# PX4FMUv1_7_1.net
KiCad netlist of a schematic drawn in EAGLE
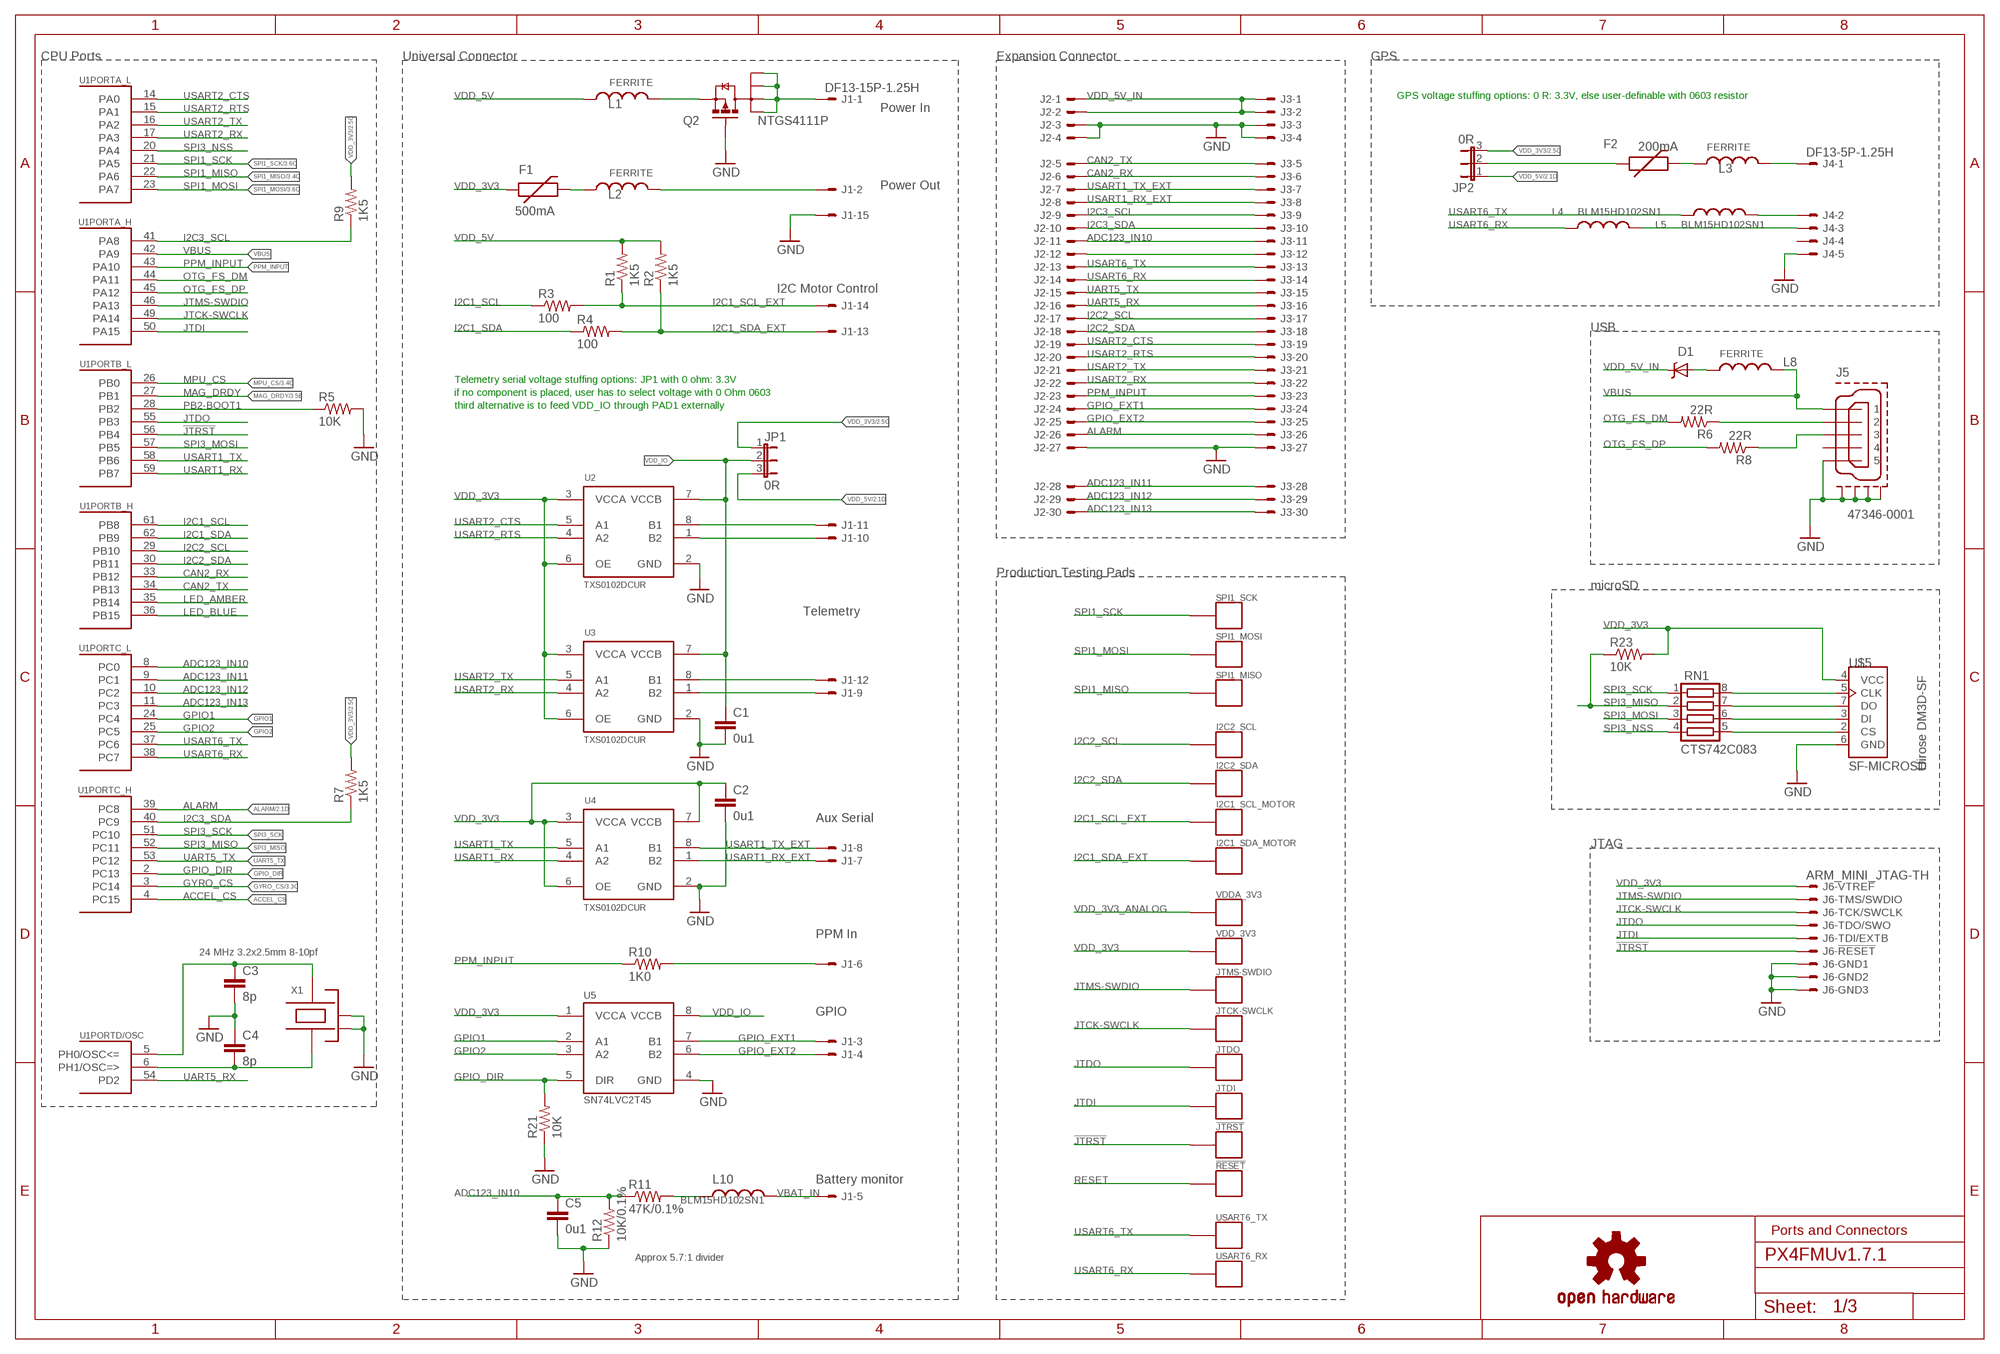
[diagram p0: schematic, sheet 1]
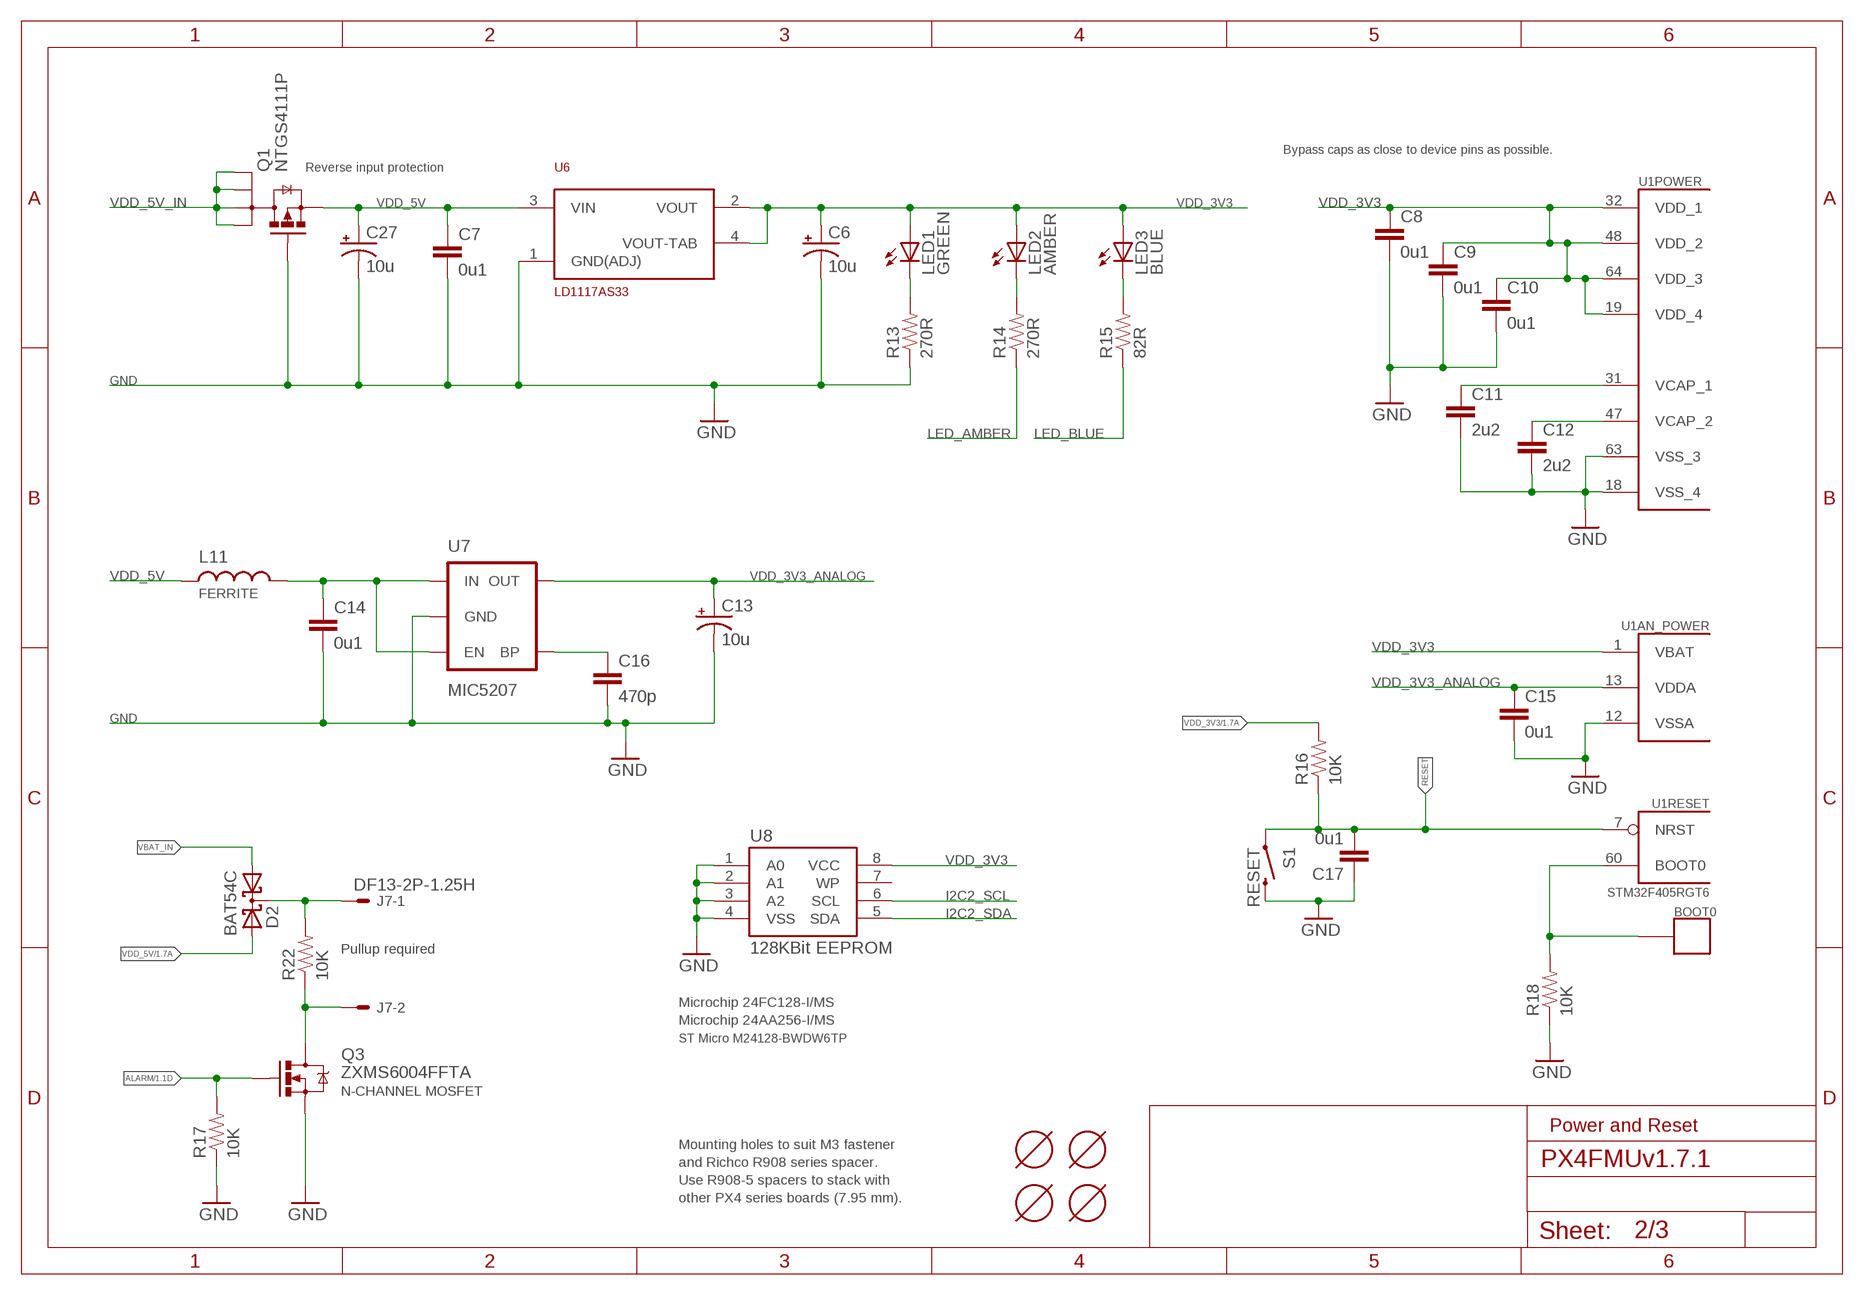
[diagram p1: schematic, sheet 2]
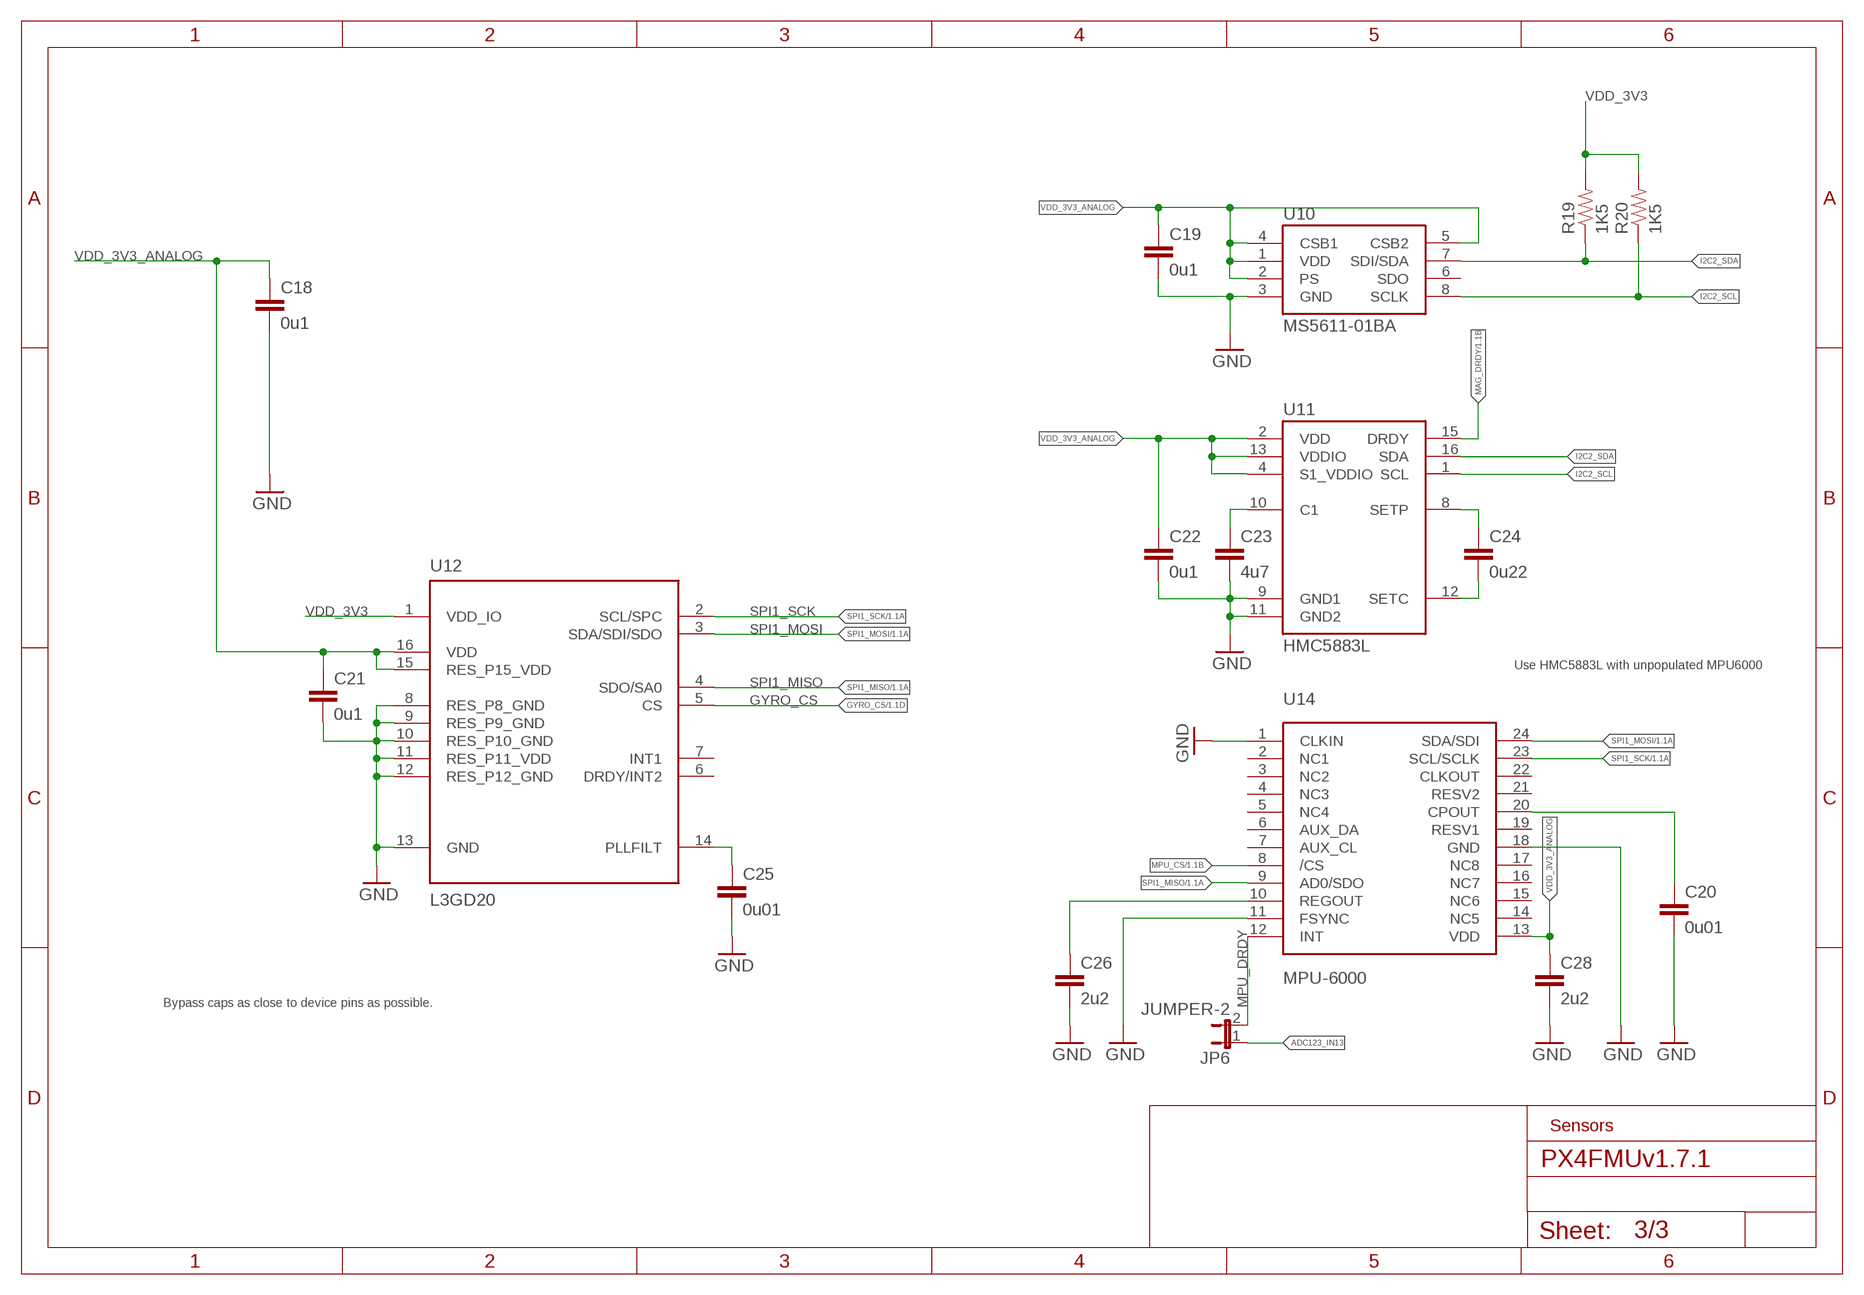
[diagram p2: schematic, sheet 3]

(export (version "E")
  (design (tool "Eeschema 10.0.6"))
  (components
    (comp (ref "C18")
      (value "0u1")
      (footprint "eagle-import:0402-CAP")
      (fields (field (name "PARTNO") "CC0402ZRY5V7BB104"))
      (libsource (lib "eagle-import") (part "CAP0402-CAP"))
    )
    (comp (ref "C19")
      (value "0u1")
      (footprint "eagle-import:0402-CAP")
      (fields (field (name "PARTNO") "CC0402ZRY5V7BB104"))
      (libsource (lib "eagle-import") (part "CAP0402-CAP"))
    )
    (comp (ref "C20")
      (value "0u01")
      (footprint "eagle-import:0402-CAP")
      (fields (field (name "PARTNO") "CC0402KRX7R7BB103"))
      (libsource (lib "eagle-import") (part "CAP0402-CAP"))
    )
    (comp (ref "C21")
      (value "0u1")
      (footprint "eagle-import:0402-CAP")
      (fields (field (name "PARTNO") "CC0402ZRY5V7BB104"))
      (libsource (lib "eagle-import") (part "CAP0402-CAP"))
    )
    (comp (ref "C22")
      (value "0u1")
      (footprint "eagle-import:0402-CAP")
      (fields (field (name "PARTNO") "CC0402ZRY5V7BB104"))
      (libsource (lib "eagle-import") (part "CAP0402-CAP"))
    )
    (comp (ref "C23")
      (value "4u7")
      (footprint "eagle-import:0402-CAP")
      (fields (field (name "PARTNO") "C1608Y5V0J475Z"))
      (libsource (lib "eagle-import") (part "CAP0402-CAP"))
    )
    (comp (ref "C24")
      (value "0u22")
      (footprint "eagle-import:0402-CAP")
      (fields (field (name "PARTNO") "C1005Y5V1C224Z"))
      (libsource (lib "eagle-import") (part "CAP0402-CAP"))
    )
    (comp (ref "C25")
      (value "0u01")
      (footprint "eagle-import:0402-CAP")
      (fields (field (name "PARTNO") "CC0402KRX7R7BB103"))
      (libsource (lib "eagle-import") (part "CAP0402-CAP"))
    )
    (comp (ref "C26")
      (value "2u2")
      (footprint "eagle-import:0402-CAP")
      (fields (field (name "PARTNO") "C1608Y5V1C225Z"))
      (libsource (lib "eagle-import") (part "CAP0402-CAP"))
    )
    (comp (ref "C28")
      (value "2u2")
      (footprint "eagle-import:0402-CAP")
      (fields (field (name "PARTNO") "C1608Y5V1C225Z"))
      (libsource (lib "eagle-import") (part "CAP0402-CAP"))
    )
    (comp (ref "JP6")
      (value "JUMPER-2")
      (footprint "eagle-import:SJ_2")
      (libsource (lib "eagle-import") (part "JUMPER-2"))
    )
    (comp (ref "R19")
      (value "1K5")
      (footprint "eagle-import:0402-RES")
      (fields (field (name "PARTNO") "RMCF0402JT1K50"))
      (libsource (lib "eagle-import") (part "RESISTOR0402-RES"))
    )
    (comp (ref "R20")
      (value "1K5")
      (footprint "eagle-import:0402-RES")
      (fields (field (name "PARTNO") "RMCF0402JT1K50"))
      (libsource (lib "eagle-import") (part "RESISTOR0402-RES"))
    )
    (comp (ref "U10")
      (value "MS5611-01BA")
      (footprint "eagle-import:MS5611-01BA")
      (libsource (lib "eagle-import") (part "MS5611-01BA"))
    )
    (comp (ref "U11")
      (value "HMC5883L")
      (footprint "eagle-import:HMC5883L-MAN")
      (libsource (lib "eagle-import") (part "HMC5883L"))
    )
    (comp (ref "U12")
      (value "L3GD20")
      (footprint "eagle-import:L3G4200DH-MAN")
      (libsource (lib "eagle-import") (part "L3G4200DH-LL"))
    )
    (comp (ref "U14")
      (value "MPU-6000")
      (footprint "eagle-import:QFN-24")
      (libsource (lib "eagle-import") (part "MPU-6000"))
    )
    (comp (ref "BOOT0")
      (value "PAD.04")
      (footprint "eagle-import:PAD.04X.04")
      (libsource (lib "eagle-import") (part "PAD.04"))
    )
    (comp (ref "C6")
      (value "10u")
      (footprint "eagle-import:EIA3216")
      (fields (field (name "PARTNO") "F931A106MAA"))
      (libsource (lib "eagle-import") (part "CAP_POL1206"))
    )
    (comp (ref "C7")
      (value "0u1")
      (footprint "eagle-import:0402-CAP")
      (fields (field (name "PARTNO") "CC0402ZRY5V7BB104"))
      (libsource (lib "eagle-import") (part "CAP0402-CAP"))
    )
    (comp (ref "C8")
      (value "0u1")
      (footprint "eagle-import:0402-CAP")
      (fields (field (name "PARTNO") "CC0402ZRY5V7BB104"))
      (libsource (lib "eagle-import") (part "CAP0402-CAP"))
    )
    (comp (ref "C9")
      (value "0u1")
      (footprint "eagle-import:0402-CAP")
      (fields (field (name "PARTNO") "CC0402ZRY5V7BB104"))
      (libsource (lib "eagle-import") (part "CAP0402-CAP"))
    )
    (comp (ref "C10")
      (value "0u1")
      (footprint "eagle-import:0402-CAP")
      (fields (field (name "PARTNO") "CC0402ZRY5V7BB104"))
      (libsource (lib "eagle-import") (part "CAP0402-CAP"))
    )
    (comp (ref "C11")
      (value "2u2")
      (footprint "eagle-import:0402-CAP")
      (fields (field (name "PARTNO") "C1608Y5V1C225Z"))
      (libsource (lib "eagle-import") (part "CAP0402-CAP"))
    )
    (comp (ref "C12")
      (value "2u2")
      (footprint "eagle-import:0402-CAP")
      (fields (field (name "PARTNO") "C1608Y5V1C225Z"))
      (libsource (lib "eagle-import") (part "CAP0402-CAP"))
    )
    (comp (ref "C13")
      (value "10u")
      (footprint "eagle-import:EIA3216")
      (fields (field (name "PARTNO") "F931A106MAA"))
      (libsource (lib "eagle-import") (part "CAP_POL1206"))
    )
    (comp (ref "C14")
      (value "0u1")
      (footprint "eagle-import:0402-CAP")
      (fields (field (name "PARTNO") "CC0402ZRY5V7BB104"))
      (libsource (lib "eagle-import") (part "CAP0402-CAP"))
    )
    (comp (ref "C15")
      (value "0u1")
      (footprint "eagle-import:0402-CAP")
      (fields (field (name "PARTNO") "CC0402ZRY5V7BB104"))
      (libsource (lib "eagle-import") (part "CAP0402-CAP"))
    )
    (comp (ref "C16")
      (value "470p")
      (footprint "eagle-import:0402-CAP")
      (fields (field (name "PARTNO") "CC0402KRX7R9BB471"))
      (libsource (lib "eagle-import") (part "CAP0402-CAP"))
    )
    (comp (ref "C17")
      (value "0u1")
      (footprint "eagle-import:0402-CAP")
      (fields (field (name "PARTNO") "CC0402ZRY5V7BB104"))
      (libsource (lib "eagle-import") (part "CAP0402-CAP"))
    )
    (comp (ref "C27")
      (value "10u")
      (footprint "eagle-import:EIA3216")
      (fields (field (name "PARTNO") "F931A106MAA"))
      (libsource (lib "eagle-import") (part "CAP_POL1206"))
    )
    (comp (ref "D2")
      (value "BAT54C")
      (footprint "eagle-import:SOT23-3")
      (fields (field (name "PARTNO") "BAT54C-7-F"))
      (libsource (lib "eagle-import") (part "BAT54C"))
    )
    (comp (ref "J7")
      (value "DF13-2P-1.25H")
      (footprint "eagle-import:DF13A-2P-1.25H")
      (fields (field (name "PARTNO") "DF13-2P-1.25H(20)"))
      (libsource (lib "eagle-import") (part "DF13-2P-1.25?H"))
    )
    (comp (ref "L11")
      (value "FERRITE")
      (footprint "eagle-import:0402-IND")
      (fields (field (name "PARTNO") "BKP1005HS121-T"))
      (libsource (lib "eagle-import") (part "INDUCTOR0402"))
    )
    (comp (ref "LED1")
      (value "GREEN")
      (footprint "eagle-import:LED-0603")
      (fields (field (name "PARTNO") "LNJ337W83RA"))
      (libsource (lib "eagle-import") (part "LED0603"))
    )
    (comp (ref "LED2")
      (value "AMBER")
      (footprint "eagle-import:LED-0603")
      (fields (field (name "PARTNO") "LNJ437W84RA"))
      (libsource (lib "eagle-import") (part "LED0603"))
    )
    (comp (ref "LED3")
      (value "BLUE")
      (footprint "eagle-import:LED-0603")
      (fields (field (name "PARTNO") "LNJ937W8CRA"))
      (libsource (lib "eagle-import") (part "LED0603"))
    )
    (comp (ref "Q1")
      (value "NTGS4111P")
      (footprint "eagle-import:TSOP-6")
      (libsource (lib "eagle-import") (part "NTGS4111P"))
    )
    (comp (ref "Q3")
      (value "ZXMS6004FFTA")
      (footprint "eagle-import:SOT23-3")
      (libsource (lib "eagle-import") (part "MOSFET-NCHANNELSMD"))
    )
    (comp (ref "R13")
      (value "270R")
      (footprint "eagle-import:0402-RES")
      (fields (field (name "PARTNO") "RC0402JR-07270RL"))
      (libsource (lib "eagle-import") (part "RESISTOR0402-RES"))
    )
    (comp (ref "R14")
      (value "270R")
      (footprint "eagle-import:0402-RES")
      (fields (field (name "PARTNO") "RC0402JR-07270RL"))
      (libsource (lib "eagle-import") (part "RESISTOR0402-RES"))
    )
    (comp (ref "R15")
      (value "82R")
      (footprint "eagle-import:0402-RES")
      (fields (field (name "PARTNO") "RC0402JR-0782RL"))
      (libsource (lib "eagle-import") (part "RESISTOR0402-RES"))
    )
    (comp (ref "R16")
      (value "10K")
      (footprint "eagle-import:0402-RES")
      (fields (field (name "PARTNO") "RMCF0402FT10K0"))
      (libsource (lib "eagle-import") (part "RESISTOR0402-RES"))
    )
    (comp (ref "R17")
      (value "10K")
      (footprint "eagle-import:0402-RES")
      (fields (field (name "PARTNO") "RMCF0402FT10K0"))
      (libsource (lib "eagle-import") (part "RESISTOR0402-RES"))
    )
    (comp (ref "R18")
      (value "10K")
      (footprint "eagle-import:0402-RES")
      (fields (field (name "PARTNO") "RMCF0402FT10K0"))
      (libsource (lib "eagle-import") (part "RESISTOR0402-RES"))
    )
    (comp (ref "R22")
      (value "10K")
      (footprint "eagle-import:0402-RES")
      (fields (field (name "PARTNO") "RMCF0402FT10K0"))
      (libsource (lib "eagle-import") (part "RESISTOR0402-RES"))
    )
    (comp (ref "S1")
      (value "RESET")
      (footprint "eagle-import:EVQP7J01K")
      (fields (field (name "PARTNO") "EVQP7J01K"))
      (libsource (lib "eagle-import") (part "SWITCH-MOMENTARY-2"))
    )
    (comp (ref "U$1")
      (value "MOUNT-HOLE3.1MM")
      (footprint "eagle-import:MOUNT-HOLE3.1")
      (libsource (lib "eagle-import") (part "MOUNT-HOLE3.1MM"))
    )
    (comp (ref "U$2")
      (value "MOUNT-HOLE3.1MM")
      (footprint "eagle-import:MOUNT-HOLE3.1")
      (libsource (lib "eagle-import") (part "MOUNT-HOLE3.1MM"))
    )
    (comp (ref "U$3")
      (value "MOUNT-HOLE3.1MM")
      (footprint "eagle-import:MOUNT-HOLE3.1")
      (libsource (lib "eagle-import") (part "MOUNT-HOLE3.1MM"))
    )
    (comp (ref "U$4")
      (value "MOUNT-HOLE3.1MM")
      (footprint "eagle-import:MOUNT-HOLE3.1")
      (libsource (lib "eagle-import") (part "MOUNT-HOLE3.1MM"))
    )
    (comp (ref "U1")
      (value "STM32F405RGT6")
      (footprint "eagle-import:TQFP64")
      (fields (field (name "PARTNO") "STM32F405RGT6"))
      (libsource (lib "eagle-import") (part "STM32F20X_TQFP64"))
    )
    (comp (ref "U6")
      (value "LD1117AS33")
      (footprint "eagle-import:SOT-223")
      (libsource (lib "eagle-import") (part "LD1117AS33"))
    )
    (comp (ref "U7")
      (value "MIC5207")
      (footprint "eagle-import:SOT23-5")
      (fields (field (name "PARTNO") "MIC5207-3.3YM5"))
      (libsource (lib "eagle-import") (part "V_REG_LDOSMD"))
    )
    (comp (ref "U8")
      (value "128KBit EEPROM")
      (footprint "eagle-import:MSOP-8")
      (fields (field (name "PARTNO") "24FC128-I/MS"))
      (libsource (lib "eagle-import") (part "EEPROM-I2CMSOP"))
    )
    (comp (ref "!JTRST")
      (value "PAD.04")
      (footprint "eagle-import:PAD.04X.04")
      (libsource (lib "eagle-import") (part "PAD.04"))
    )
    (comp (ref "!RESET")
      (value "PAD.04")
      (footprint "eagle-import:PAD.04X.04")
      (libsource (lib "eagle-import") (part "PAD.04"))
    )
    (comp (ref "C1")
      (value "0u1")
      (footprint "eagle-import:0402-CAP")
      (fields (field (name "PARTNO") "CC0402ZRY5V7BB104"))
      (libsource (lib "eagle-import") (part "CAP0402-CAP"))
    )
    (comp (ref "C2")
      (value "0u1")
      (footprint "eagle-import:0402-CAP")
      (fields (field (name "PARTNO") "CC0402ZRY5V7BB104"))
      (libsource (lib "eagle-import") (part "CAP0402-CAP"))
    )
    (comp (ref "C3")
      (value "8p")
      (footprint "eagle-import:0402-CAP")
      (fields (field (name "PARTNO") "C1005C0G1H080C"))
      (libsource (lib "eagle-import") (part "CAP0402-CAP"))
    )
    (comp (ref "C4")
      (value "8p")
      (footprint "eagle-import:0402-CAP")
      (fields (field (name "PARTNO") "C1005C0G1H080C"))
      (libsource (lib "eagle-import") (part "CAP0402-CAP"))
    )
    (comp (ref "C5")
      (value "0u1")
      (footprint "eagle-import:0402-CAP")
      (fields (field (name "PARTNO") "CC0402ZRY5V7BB104"))
      (libsource (lib "eagle-import") (part "CAP0402-CAP"))
    )
    (comp (ref "D1")
      (value "MSS1P4-M3")
      (footprint "eagle-import:MICROSMP")
      (fields (field (name "PARTNO") "MSS1P4-M3/89A"))
      (libsource (lib "eagle-import") (part "DIODE-SCHOTTKY_MSMP"))
    )
    (comp (ref "F1")
      (value "500mA")
      (footprint "eagle-import:0402-PTC")
      (fields (field (name "PARTNO") "MF-FSMF050X-2"))
      (libsource (lib "eagle-import") (part "PTC0402"))
    )
    (comp (ref "F2")
      (value "200mA")
      (footprint "eagle-import:0402-PTC")
      (fields (field (name "PARTNO") "MF-FSMF020X-2"))
      (libsource (lib "eagle-import") (part "PTC0402"))
    )
    (comp (ref "I2C1_SCL_MOTOR")
      (value "PAD.03")
      (footprint "eagle-import:PAD.03X.03")
      (libsource (lib "eagle-import") (part "PAD.03"))
    )
    (comp (ref "I2C1_SDA_MOTOR")
      (value "PAD.03")
      (footprint "eagle-import:PAD.03X.03")
      (libsource (lib "eagle-import") (part "PAD.03"))
    )
    (comp (ref "I2C2_SCL")
      (value "PAD.03")
      (footprint "eagle-import:PAD.03X.03")
      (libsource (lib "eagle-import") (part "PAD.03"))
    )
    (comp (ref "I2C2_SDA")
      (value "PAD.04")
      (footprint "eagle-import:PAD.04X.04")
      (libsource (lib "eagle-import") (part "PAD.04"))
    )
    (comp (ref "J1")
      (value "DF13-15P-1.25H")
      (footprint "eagle-import:DF13A-15P-1.25H")
      (fields (field (name "PARTNO") "DF13A-15P-1.25H(20)"))
      (libsource (lib "eagle-import") (part "DF13-15P-1.25?H"))
    )
    (comp (ref "J2")
      (value "HEADER_2X15-REV")
      (footprint "eagle-import:HEADER_2MM_2X15_REVERSE")
      (fields (field (name "BOM") "EXCLUDE") (field (name "PARTNO") "953230-2000-AR-PR"))
      (libsource (lib "eagle-import") (part "HEADER_2X15-REV"))
    )
    (comp (ref "J3")
      (value "HEADER_2X15")
      (footprint "eagle-import:HEADER_2MM_2X15")
      (fields (field (name "PARTNO") "953230-2000-AR-PR"))
      (libsource (lib "eagle-import") (part "HEADER_2X15-SMD"))
    )
    (comp (ref "J4")
      (value "DF13-5P-1.25H")
      (footprint "eagle-import:DF13A-5P-1.25H")
      (fields (field (name "PARTNO") "DF13A-5P-1.25H(20)"))
      (libsource (lib "eagle-import") (part "DF13-5P-1.25?H"))
    )
    (comp (ref "J5")
      (value "47346-0001")
      (footprint "eagle-import:MOLEX-47346-0001")
      (libsource (lib "eagle-import") (part "MOLEX-47346-0001"))
    )
    (comp (ref "J6")
      (value "ARM_MINI_JTAG-TH")
      (footprint "eagle-import:FTSH-105-01-XXX-DV")
      (fields (field (name "PARTNO") "M50-3900542"))
      (libsource (lib "eagle-import") (part "ARM_MINI_JTAG-TH"))
    )
    (comp (ref "JP1")
      (value "0R")
      (footprint "eagle-import:SJ_3_0603_PASTE1&2")
      (fields (field (name "PARTNO") "RMCF0402ZT0R00"))
      (libsource (lib "eagle-import") (part "JUMPER-30603"))
    )
    (comp (ref "JP2")
      (value "0R")
      (footprint "eagle-import:SJ_3_0603_PASTE1&2")
      (fields (field (name "PARTNO") "RMCF0402ZT0R00"))
      (libsource (lib "eagle-import") (part "JUMPER-30603"))
    )
    (comp (ref "JTCK-SWCLK")
      (value "PAD.04")
      (footprint "eagle-import:PAD.04X.04")
      (libsource (lib "eagle-import") (part "PAD.04"))
    )
    (comp (ref "JTDI")
      (value "PAD.04")
      (footprint "eagle-import:PAD.04X.04")
      (libsource (lib "eagle-import") (part "PAD.04"))
    )
    (comp (ref "JTDO")
      (value "PAD.04")
      (footprint "eagle-import:PAD.04X.04")
      (libsource (lib "eagle-import") (part "PAD.04"))
    )
    (comp (ref "JTMS-SWDIO")
      (value "PAD.04")
      (footprint "eagle-import:PAD.04X.04")
      (libsource (lib "eagle-import") (part "PAD.04"))
    )
    (comp (ref "L1")
      (value "FERRITE")
      (footprint "eagle-import:0402-IND")
      (fields (field (name "PARTNO") "BKP1005HS121-T"))
      (libsource (lib "eagle-import") (part "INDUCTOR0402"))
    )
    (comp (ref "L2")
      (value "FERRITE")
      (footprint "eagle-import:0402-IND")
      (fields (field (name "PARTNO") "BKP1005HS121-T"))
      (libsource (lib "eagle-import") (part "INDUCTOR0402"))
    )
    (comp (ref "L3")
      (value "FERRITE")
      (footprint "eagle-import:0402-IND")
      (fields (field (name "PARTNO") "BKP1005HS121-T"))
      (libsource (lib "eagle-import") (part "INDUCTOR0402"))
    )
    (comp (ref "L4")
      (value "BLM15HD102SN1")
      (footprint "eagle-import:0402-IND")
      (libsource (lib "eagle-import") (part "INDUCTOR0402"))
    )
    (comp (ref "L5")
      (value "BLM15HD102SN1")
      (footprint "eagle-import:0402-IND")
      (libsource (lib "eagle-import") (part "INDUCTOR0402"))
    )
    (comp (ref "L8")
      (value "FERRITE")
      (footprint "eagle-import:0402-IND")
      (fields (field (name "PARTNO") "BKP1005HS121-T"))
      (libsource (lib "eagle-import") (part "INDUCTOR0402"))
    )
    (comp (ref "L10")
      (value "BLM15HD102SN1")
      (footprint "eagle-import:0402-IND")
      (libsource (lib "eagle-import") (part "INDUCTOR0402"))
    )
    (comp (ref "Q2")
      (value "NTGS4111P")
      (footprint "eagle-import:TSOP-6")
      (libsource (lib "eagle-import") (part "NTGS4111P"))
    )
    (comp (ref "R1")
      (value "1K5")
      (footprint "eagle-import:0402-RES")
      (fields (field (name "PARTNO") "RMCF0402JT1K50"))
      (libsource (lib "eagle-import") (part "RESISTOR0402-RES"))
    )
    (comp (ref "R2")
      (value "1K5")
      (footprint "eagle-import:0402-RES")
      (fields (field (name "PARTNO") "RMCF0402JT1K50"))
      (libsource (lib "eagle-import") (part "RESISTOR0402-RES"))
    )
    (comp (ref "R3")
      (value "100")
      (footprint "eagle-import:0402-RES")
      (fields (field (name "PARTNO") "RMCF0402JT100R"))
      (libsource (lib "eagle-import") (part "RESISTOR0402-RES"))
    )
    (comp (ref "R4")
      (value "100")
      (footprint "eagle-import:0402-RES")
      (fields (field (name "PARTNO") "RMCF0402JT100R"))
      (libsource (lib "eagle-import") (part "RESISTOR0402-RES"))
    )
    (comp (ref "R5")
      (value "10K")
      (footprint "eagle-import:0402-RES")
      (fields (field (name "PARTNO") "RMCF0402FT10K0"))
      (libsource (lib "eagle-import") (part "RESISTOR0402-RES"))
    )
    (comp (ref "R6")
      (value "22R")
      (footprint "eagle-import:0402-RES")
      (fields (field (name "PARTNO") "RMCF0402JT22R0"))
      (libsource (lib "eagle-import") (part "RESISTOR0402-RES"))
    )
    (comp (ref "R7")
      (value "1K5")
      (footprint "eagle-import:0402-RES")
      (fields (field (name "PARTNO") "RMCF0402JT1K50"))
      (libsource (lib "eagle-import") (part "RESISTOR0402-RES"))
    )
    (comp (ref "R8")
      (value "22R")
      (footprint "eagle-import:0402-RES")
      (fields (field (name "PARTNO") "RMCF0402JT22R0"))
      (libsource (lib "eagle-import") (part "RESISTOR0402-RES"))
    )
    (comp (ref "R9")
      (value "1K5")
      (footprint "eagle-import:0402-RES")
      (fields (field (name "PARTNO") "RMCF0402JT1K50"))
      (libsource (lib "eagle-import") (part "RESISTOR0402-RES"))
    )
    (comp (ref "R10")
      (value "1K0")
      (footprint "eagle-import:0402-RES")
      (fields (field (name "PARTNO") "RMCF0402JT1K00"))
      (libsource (lib "eagle-import") (part "RESISTOR0402-RES"))
    )
    (comp (ref "R11")
      (value "47K/0.1%")
      (footprint "eagle-import:0402-RES")
      (fields (field (name "PARTNO") "ERA-2AEB473X"))
      (libsource (lib "eagle-import") (part "RESISTOR0402-RES"))
    )
    (comp (ref "R12")
      (value "10K/0.1%")
      (footprint "eagle-import:0402-RES")
      (fields (field (name "PARTNO") "ERA-2AEB103X"))
      (libsource (lib "eagle-import") (part "RESISTOR0402-RES"))
    )
    (comp (ref "R21")
      (value "10K")
      (footprint "eagle-import:0402-RES")
      (fields (field (name "PARTNO") "RMCF0402FT10K0"))
      (libsource (lib "eagle-import") (part "RESISTOR0402-RES"))
    )
    (comp (ref "R23")
      (value "10K")
      (footprint "eagle-import:0402-RES")
      (fields (field (name "PARTNO") "RMCF0402FT10K0"))
      (libsource (lib "eagle-import") (part "RESISTOR0402-RES"))
    )
    (comp (ref "RN1")
      (value "CTS742C083")
      (footprint "eagle-import:CTS742C083")
      (fields (field (name "PARTNO") "TC164-JR-07100RL"))
      (libsource (lib "eagle-import") (part "CTS742C083"))
    )
    (comp (ref "SPI1_MISO")
      (value "PAD.04")
      (footprint "eagle-import:PAD.04X.04")
      (libsource (lib "eagle-import") (part "PAD.04"))
    )
    (comp (ref "SPI1_MOSI")
      (value "PAD.04")
      (footprint "eagle-import:PAD.04X.04")
      (libsource (lib "eagle-import") (part "PAD.04"))
    )
    (comp (ref "SPI1_SCK")
      (value "PAD.04")
      (footprint "eagle-import:PAD.04X.04")
      (libsource (lib "eagle-import") (part "PAD.04"))
    )
    (comp (ref "U$5")
      (value "SF-MICROSD")
      (footprint "eagle-import:MICROSD")
      (libsource (lib "eagle-import") (part "SF-MICROSD"))
    )
    (comp (ref "U$7")
      (value "OSHW-LOGOS")
      (footprint "eagle-import:OSHW-LOGO-S")
      (libsource (lib "eagle-import") (part "OSHW-LOGOS"))
    )
    (comp (ref "U2")
      (value "TXS0102DCUR")
      (footprint "eagle-import:TI-DCU")
      (libsource (lib "eagle-import") (part "TXS0102DCUR"))
    )
    (comp (ref "U3")
      (value "TXS0102DCUR")
      (footprint "eagle-import:TI-DCU")
      (libsource (lib "eagle-import") (part "TXS0102DCUR"))
    )
    (comp (ref "U4")
      (value "TXS0102DCUR")
      (footprint "eagle-import:TI-DCU")
      (libsource (lib "eagle-import") (part "TXS0102DCUR"))
    )
    (comp (ref "U5")
      (value "SN74LVC2T45")
      (footprint "eagle-import:TI-DCU")
      (libsource (lib "eagle-import") (part "SN74LVC2T45DCUR"))
    )
    (comp (ref "USART6_RX")
      (value "PAD.04")
      (footprint "eagle-import:PAD.04X.04")
      (libsource (lib "eagle-import") (part "PAD.04"))
    )
    (comp (ref "USART6_TX")
      (value "PAD.04")
      (footprint "eagle-import:PAD.04X.04")
      (libsource (lib "eagle-import") (part "PAD.04"))
    )
    (comp (ref "VDDA_3V3")
      (value "PAD.04")
      (footprint "eagle-import:PAD.04X.04")
      (libsource (lib "eagle-import") (part "PAD.04"))
    )
    (comp (ref "VDD_3V3")
      (value "PAD.04")
      (footprint "eagle-import:PAD.04X.04")
      (libsource (lib "eagle-import") (part "PAD.04"))
    )
    (comp (ref "X1")
      (value "24 MHz 3.2x2.5mm 8-10pf")
      (footprint "eagle-import:OSCILLATOR-3.2X2.5")
      (fields (field (name "PARTNO") "NX3225SA-24.000000MHZ"))
      (libsource (lib "eagle-import") (part "OSCILLATOR-3.2X2.5"))
    )
  )
  (nets
    (net (code "1") (name "ACCEL_CS") (class "Default")
      (node (ref "U1") (pin "4") (pinfunction "PC15_4") (pintype "bidirectional"))
    )
    (net (code "2") (name "ADC123_IN10") (class "Default")
      (node (ref "C5") (pin "1") (pinfunction "1_1") (pintype "passive"))
      (node (ref "J2") (pin "11") (pinfunction "S_11") (pintype "passive"))
      (node (ref "J3") (pin "11") (pinfunction "S_11") (pintype "passive"))
      (node (ref "R11") (pin "1") (pinfunction "1_1") (pintype "passive"))
      (node (ref "R12") (pin "2") (pinfunction "2_2") (pintype "passive"))
      (node (ref "U1") (pin "8") (pinfunction "PC0_8") (pintype "bidirectional"))
    )
    (net (code "3") (name "ADC123_IN11") (class "Default")
      (node (ref "J2") (pin "28") (pinfunction "S_28") (pintype "passive"))
      (node (ref "J3") (pin "28") (pinfunction "S_28") (pintype "passive"))
      (node (ref "U1") (pin "9") (pinfunction "PC1_9") (pintype "bidirectional"))
    )
    (net (code "4") (name "ADC123_IN12") (class "Default")
      (node (ref "J2") (pin "29") (pinfunction "S_29") (pintype "passive"))
      (node (ref "J3") (pin "29") (pinfunction "S_29") (pintype "passive"))
      (node (ref "U1") (pin "10") (pinfunction "PC2_10") (pintype "bidirectional"))
    )
    (net (code "5") (name "ADC123_IN13") (class "Default")
      (node (ref "J2") (pin "30") (pinfunction "S_30") (pintype "passive"))
      (node (ref "J3") (pin "30") (pinfunction "S_30") (pintype "passive"))
      (node (ref "JP6") (pin "1") (pinfunction "1_1") (pintype "passive"))
      (node (ref "U1") (pin "11") (pinfunction "PC3_11") (pintype "bidirectional"))
    )
    (net (code "6") (name "ALARM") (class "Default")
      (node (ref "J2") (pin "26") (pinfunction "S_26") (pintype "passive"))
      (node (ref "J3") (pin "26") (pinfunction "S_26") (pintype "passive"))
      (node (ref "Q3") (pin "1") (pinfunction "G_1") (pintype "passive"))
      (node (ref "R17") (pin "2") (pinfunction "2_2") (pintype "passive"))
      (node (ref "U1") (pin "39") (pinfunction "PC8_39") (pintype "bidirectional"))
    )
    (net (code "7") (name "CAN2_RX") (class "Default")
      (node (ref "J2") (pin "6") (pinfunction "S_6") (pintype "passive"))
      (node (ref "J3") (pin "6") (pinfunction "S_6") (pintype "passive"))
      (node (ref "U1") (pin "33") (pinfunction "PB12_33") (pintype "bidirectional"))
    )
    (net (code "8") (name "CAN2_TX") (class "Default")
      (node (ref "J2") (pin "5") (pinfunction "S_5") (pintype "passive"))
      (node (ref "J3") (pin "5") (pinfunction "S_5") (pintype "passive"))
      (node (ref "U1") (pin "34") (pinfunction "PB13_34") (pintype "bidirectional"))
    )
    (net (code "9") (name "GND") (class "Default")
      (node (ref "C1") (pin "2") (pinfunction "2_2") (pintype "passive"))
      (node (ref "C10") (pin "2") (pinfunction "2_2") (pintype "passive"))
      (node (ref "C11") (pin "2") (pinfunction "2_2") (pintype "passive"))
      (node (ref "C12") (pin "2") (pinfunction "2_2") (pintype "passive"))
      (node (ref "C13") (pin "C") (pinfunction "-_C") (pintype "passive"))
      (node (ref "C14") (pin "2") (pinfunction "2_2") (pintype "passive"))
      (node (ref "C15") (pin "2") (pinfunction "2_2") (pintype "passive"))
      (node (ref "C16") (pin "2") (pinfunction "2_2") (pintype "passive"))
      (node (ref "C17") (pin "1") (pinfunction "1_1") (pintype "passive"))
      (node (ref "C18") (pin "2") (pinfunction "2_2") (pintype "passive"))
      (node (ref "C19") (pin "2") (pinfunction "2_2") (pintype "passive"))
      (node (ref "C2") (pin "2") (pinfunction "2_2") (pintype "passive"))
      (node (ref "C20") (pin "2") (pinfunction "2_2") (pintype "passive"))
      (node (ref "C21") (pin "2") (pinfunction "2_2") (pintype "passive"))
      (node (ref "C22") (pin "2") (pinfunction "2_2") (pintype "passive"))
      (node (ref "C23") (pin "2") (pinfunction "2_2") (pintype "passive"))
      (node (ref "C25") (pin "2") (pinfunction "2_2") (pintype "passive"))
      (node (ref "C26") (pin "2") (pinfunction "2_2") (pintype "passive"))
      (node (ref "C27") (pin "C") (pinfunction "-_C") (pintype "passive"))
      (node (ref "C28") (pin "2") (pinfunction "2_2") (pintype "passive"))
      (node (ref "C3") (pin "2") (pinfunction "2_2") (pintype "passive"))
      (node (ref "C4") (pin "1") (pinfunction "1_1") (pintype "passive"))
      (node (ref "C5") (pin "2") (pinfunction "2_2") (pintype "passive"))
      (node (ref "C6") (pin "C") (pinfunction "-_C") (pintype "passive"))
      (node (ref "C7") (pin "2") (pinfunction "2_2") (pintype "passive"))
      (node (ref "C8") (pin "2") (pinfunction "2_2") (pintype "passive"))
      (node (ref "C9") (pin "2") (pinfunction "2_2") (pintype "passive"))
      (node (ref "J1") (pin "15") (pinfunction "S_15") (pintype "passive"))
      (node (ref "J2") (pin "27") (pinfunction "S_27") (pintype "passive"))
      (node (ref "J2") (pin "3") (pinfunction "S_3") (pintype "passive"))
      (node (ref "J2") (pin "4") (pinfunction "S_4") (pintype "passive"))
      (node (ref "J3") (pin "27") (pinfunction "S_27") (pintype "passive"))
      (node (ref "J3") (pin "3") (pinfunction "S_3") (pintype "passive"))
      (node (ref "J3") (pin "4") (pinfunction "S_4") (pintype "passive"))
      (node (ref "J4") (pin "5") (pinfunction "S_5") (pintype "passive"))
      (node (ref "J5") (pin "GND") (pinfunction "5_GND") (pintype "power_in"))
      (node (ref "J5") (pin "GND1") (pinfunction "GND1_GND1") (pintype "bidirectional"))
      (node (ref "J5") (pin "GND2") (pinfunction "GND2_GND2") (pintype "bidirectional"))
      (node (ref "J5") (pin "GND3") (pinfunction "GND3_GND3") (pintype "bidirectional"))
      (node (ref "J5") (pin "GND4") (pinfunction "GND4_GND4") (pintype "bidirectional"))
      (node (ref "J6") (pin "3") (pinfunction "S_3") (pintype "passive"))
      (node (ref "J6") (pin "5") (pinfunction "S_5") (pintype "passive"))
      (node (ref "J6") (pin "9") (pinfunction "S_9") (pintype "passive"))
      (node (ref "Q1") (pin "3") (pinfunction "G_3") (pintype "passive"))
      (node (ref "Q2") (pin "3") (pinfunction "G_3") (pintype "passive"))
      (node (ref "Q3") (pin "2") (pinfunction "S_2") (pintype "passive"))
      (node (ref "R12") (pin "1") (pinfunction "1_1") (pintype "passive"))
      (node (ref "R13") (pin "1") (pinfunction "1_1") (pintype "passive"))
      (node (ref "R17") (pin "1") (pinfunction "1_1") (pintype "passive"))
      (node (ref "R18") (pin "1") (pinfunction "1_1") (pintype "passive"))
      (node (ref "R21") (pin "1") (pinfunction "1_1") (pintype "passive"))
      (node (ref "R5") (pin "2") (pinfunction "2_2") (pintype "passive"))
      (node (ref "S1") (pin "B3") (pinfunction "2_B3") (pintype "passive"))
      (node (ref "U$5") (pin "6") (pinfunction "GND_6") (pintype "power_in"))
      (node (ref "U1") (pin "12") (pinfunction "VSSA_12") (pintype "power_in"))
      (node (ref "U1") (pin "18") (pinfunction "VSS_4_18") (pintype "power_in"))
      (node (ref "U1") (pin "63") (pinfunction "VSS_3_63") (pintype "power_in"))
      (node (ref "U10") (pin "3") (pinfunction "GND_3") (pintype "bidirectional"))
      (node (ref "U11") (pin "11") (pinfunction "GND2_11") (pintype "bidirectional"))
      (node (ref "U11") (pin "9") (pinfunction "GND1_9") (pintype "bidirectional"))
      (node (ref "U12") (pin "10") (pinfunction "RES_P10_GND_10") (pintype "bidirectional"))
      (node (ref "U12") (pin "11") (pinfunction "RES_P11_VDD_11") (pintype "bidirectional"))
      (node (ref "U12") (pin "12") (pinfunction "RES_P12_GND_12") (pintype "bidirectional"))
      (node (ref "U12") (pin "13") (pinfunction "GND_13") (pintype "bidirectional"))
      (node (ref "U12") (pin "8") (pinfunction "RES_P8_GND_8") (pintype "bidirectional"))
      (node (ref "U12") (pin "9") (pinfunction "RES_P9_GND_9") (pintype "bidirectional"))
      (node (ref "U14") (pin "1") (pinfunction "CLKIN_1") (pintype "bidirectional"))
      (node (ref "U14") (pin "11") (pinfunction "FSYNC_11") (pintype "bidirectional"))
      (node (ref "U14") (pin "18") (pinfunction "GND_18") (pintype "bidirectional"))
      (node (ref "U2") (pin "2") (pinfunction "GND_2") (pintype "power_in"))
      (node (ref "U3") (pin "2") (pinfunction "GND_2") (pintype "power_in"))
      (node (ref "U4") (pin "2") (pinfunction "GND_2") (pintype "power_in"))
      (node (ref "U5") (pin "4") (pinfunction "GND_4") (pintype "power_in"))
      (node (ref "U6") (pin "1") (pinfunction "GND(ADJ)_1") (pintype "bidirectional"))
      (node (ref "U7") (pin "2") (pinfunction "GND_2") (pintype "input"))
      (node (ref "U8") (pin "1") (pinfunction "A0_1") (pintype "bidirectional"))
      (node (ref "U8") (pin "2") (pinfunction "A1_2") (pintype "bidirectional"))
      (node (ref "U8") (pin "3") (pinfunction "A2_3") (pintype "bidirectional"))
      (node (ref "U8") (pin "4") (pinfunction "VSS_4") (pintype "power_in"))
      (node (ref "X1") (pin "2") (pinfunction "NC_2_2") (pintype "power_in"))
      (node (ref "X1") (pin "4") (pinfunction "NC_4_4") (pintype "power_in"))
    )
    (net (code "10") (name "GPIO1") (class "Default")
      (node (ref "U1") (pin "24") (pinfunction "PC4_24") (pintype "bidirectional"))
      (node (ref "U5") (pin "2") (pinfunction "A1_2") (pintype "bidirectional"))
    )
    (net (code "11") (name "GPIO2") (class "Default")
      (node (ref "U1") (pin "25") (pinfunction "PC5_25") (pintype "bidirectional"))
      (node (ref "U5") (pin "3") (pinfunction "A2_3") (pintype "bidirectional"))
    )
    (net (code "12") (name "GPIO_DIR") (class "Default")
      (node (ref "R21") (pin "2") (pinfunction "2_2") (pintype "passive"))
      (node (ref "U1") (pin "2") (pinfunction "PC13_2") (pintype "bidirectional"))
      (node (ref "U5") (pin "5") (pinfunction "DIR_5") (pintype "input"))
    )
    (net (code "13") (name "GPIO_EXT1") (class "Default")
      (node (ref "J1") (pin "3") (pinfunction "S_3") (pintype "passive"))
      (node (ref "J2") (pin "24") (pinfunction "S_24") (pintype "passive"))
      (node (ref "J3") (pin "24") (pinfunction "S_24") (pintype "passive"))
      (node (ref "U5") (pin "7") (pinfunction "B1_7") (pintype "bidirectional"))
    )
    (net (code "14") (name "GPIO_EXT2") (class "Default")
      (node (ref "J1") (pin "4") (pinfunction "S_4") (pintype "passive"))
      (node (ref "J2") (pin "25") (pinfunction "S_25") (pintype "passive"))
      (node (ref "J3") (pin "25") (pinfunction "S_25") (pintype "passive"))
      (node (ref "U5") (pin "6") (pinfunction "B2_6") (pintype "bidirectional"))
    )
    (net (code "15") (name "GYRO_CS") (class "Default")
      (node (ref "U1") (pin "3") (pinfunction "PC14_3") (pintype "bidirectional"))
      (node (ref "U12") (pin "5") (pinfunction "CS_5") (pintype "input"))
    )
    (net (code "16") (name "I2C1_SCL") (class "Default")
      (node (ref "R3") (pin "1") (pinfunction "1_1") (pintype "passive"))
      (node (ref "U1") (pin "61") (pinfunction "PB8_61") (pintype "bidirectional"))
    )
    (net (code "17") (name "I2C1_SCL_EXT") (class "Default")
      (node (ref "I2C1_SCL_MOTOR") (pin "P$1") (pinfunction "P$1_P$1") (pintype "passive"))
      (node (ref "J1") (pin "14") (pinfunction "S_14") (pintype "passive"))
      (node (ref "R1") (pin "1") (pinfunction "1_1") (pintype "passive"))
      (node (ref "R3") (pin "2") (pinfunction "2_2") (pintype "passive"))
    )
    (net (code "18") (name "I2C1_SDA") (class "Default")
      (node (ref "R4") (pin "1") (pinfunction "1_1") (pintype "passive"))
      (node (ref "U1") (pin "62") (pinfunction "PB9_62") (pintype "bidirectional"))
    )
    (net (code "19") (name "I2C1_SDA_EXT") (class "Default")
      (node (ref "I2C1_SDA_MOTOR") (pin "P$1") (pinfunction "P$1_P$1") (pintype "passive"))
      (node (ref "J1") (pin "13") (pinfunction "S_13") (pintype "passive"))
      (node (ref "R2") (pin "1") (pinfunction "1_1") (pintype "passive"))
      (node (ref "R4") (pin "2") (pinfunction "2_2") (pintype "passive"))
    )
    (net (code "20") (name "I2C2_SCL") (class "Default")
      (node (ref "I2C2_SCL") (pin "P$1") (pinfunction "P$1_P$1") (pintype "passive"))
      (node (ref "J2") (pin "17") (pinfunction "S_17") (pintype "passive"))
      (node (ref "J3") (pin "17") (pinfunction "S_17") (pintype "passive"))
      (node (ref "R20") (pin "1") (pinfunction "1_1") (pintype "passive"))
      (node (ref "U1") (pin "29") (pinfunction "PB10_29") (pintype "bidirectional"))
      (node (ref "U10") (pin "8") (pinfunction "SCLK_8") (pintype "bidirectional"))
      (node (ref "U11") (pin "1") (pinfunction "SCL_1") (pintype "bidirectional"))
      (node (ref "U8") (pin "6") (pinfunction "SCL_6") (pintype "bidirectional"))
    )
    (net (code "21") (name "I2C2_SDA") (class "Default")
      (node (ref "I2C2_SDA") (pin "P$1") (pinfunction "P$1_P$1") (pintype "passive"))
      (node (ref "J2") (pin "18") (pinfunction "S_18") (pintype "passive"))
      (node (ref "J3") (pin "18") (pinfunction "S_18") (pintype "passive"))
      (node (ref "R19") (pin "1") (pinfunction "1_1") (pintype "passive"))
      (node (ref "U1") (pin "30") (pinfunction "PB11_30") (pintype "bidirectional"))
      (node (ref "U10") (pin "7") (pinfunction "SDI/SDA_7") (pintype "bidirectional"))
      (node (ref "U11") (pin "16") (pinfunction "SDA_16") (pintype "bidirectional"))
      (node (ref "U8") (pin "5") (pinfunction "SDA_5") (pintype "bidirectional"))
    )
    (net (code "22") (name "I2C3_SCL") (class "Default")
      (node (ref "J2") (pin "9") (pinfunction "S_9") (pintype "passive"))
      (node (ref "J3") (pin "9") (pinfunction "S_9") (pintype "passive"))
      (node (ref "R9") (pin "1") (pinfunction "1_1") (pintype "passive"))
      (node (ref "U1") (pin "41") (pinfunction "PA8_41") (pintype "bidirectional"))
    )
    (net (code "23") (name "I2C3_SDA") (class "Default")
      (node (ref "J2") (pin "10") (pinfunction "S_10") (pintype "passive"))
      (node (ref "J3") (pin "10") (pinfunction "S_10") (pintype "passive"))
      (node (ref "R7") (pin "1") (pinfunction "1_1") (pintype "passive"))
      (node (ref "U1") (pin "40") (pinfunction "PC9_40") (pintype "bidirectional"))
    )
    (net (code "24") (name "JTCK-SWCLK") (class "Default")
      (node (ref "J6") (pin "4") (pinfunction "S_4") (pintype "passive"))
      (node (ref "JTCK-SWCLK") (pin "P$1") (pinfunction "P$1_P$1") (pintype "passive"))
      (node (ref "U1") (pin "49") (pinfunction "PA14_49") (pintype "bidirectional"))
    )
    (net (code "25") (name "JTDI") (class "Default")
      (node (ref "J6") (pin "8") (pinfunction "S_8") (pintype "passive"))
      (node (ref "JTDI") (pin "P$1") (pinfunction "P$1_P$1") (pintype "passive"))
      (node (ref "U1") (pin "50") (pinfunction "PA15_50") (pintype "bidirectional"))
    )
    (net (code "26") (name "JTDO") (class "Default")
      (node (ref "J6") (pin "6") (pinfunction "S_6") (pintype "passive"))
      (node (ref "JTDO") (pin "P$1") (pinfunction "P$1_P$1") (pintype "passive"))
      (node (ref "U1") (pin "55") (pinfunction "PB3_55") (pintype "bidirectional"))
    )
    (net (code "27") (name "JTMS-SWDIO") (class "Default")
      (node (ref "J6") (pin "2") (pinfunction "S_2") (pintype "passive"))
      (node (ref "JTMS-SWDIO") (pin "P$1") (pinfunction "P$1_P$1") (pintype "passive"))
      (node (ref "U1") (pin "46") (pinfunction "PA13_46") (pintype "bidirectional"))
    )
    (net (code "28") (name "LED_AMBER") (class "Default")
      (node (ref "R14") (pin "1") (pinfunction "1_1") (pintype "passive"))
      (node (ref "U1") (pin "35") (pinfunction "PB14_35") (pintype "bidirectional"))
    )
    (net (code "29") (name "LED_BLUE") (class "Default")
      (node (ref "R15") (pin "1") (pinfunction "1_1") (pintype "passive"))
      (node (ref "U1") (pin "36") (pinfunction "PB15_36") (pintype "bidirectional"))
    )
    (net (code "30") (name "MAG_DRDY") (class "Default")
      (node (ref "U1") (pin "27") (pinfunction "PB1_27") (pintype "bidirectional"))
      (node (ref "U11") (pin "15") (pinfunction "DRDY_15") (pintype "bidirectional"))
    )
    (net (code "31") (name "MPU_CS") (class "Default")
      (node (ref "U1") (pin "26") (pinfunction "PB0_26") (pintype "bidirectional"))
      (node (ref "U14") (pin "8") (pinfunction "/CS_8") (pintype "bidirectional"))
    )
    (net (code "32") (name "Net-(D1-A)") (class "Default")
      (node (ref "D1") (pin "ANODE") (pinfunction "A_ANODE") (pintype "passive"))
      (node (ref "L8") (pin "1") (pinfunction "1_1") (pintype "passive"))
    )
    (net (code "33") (name "Net-(D2-CC)") (class "Default")
      (node (ref "D2") (pin "3") (pinfunction "CC_3") (pintype "passive"))
      (node (ref "J7") (pin "1") (pinfunction "S_1") (pintype "passive"))
      (node (ref "R22") (pin "2") (pinfunction "2_2") (pintype "passive"))
    )
    (net (code "34") (name "Net-(F1-Pad2)") (class "Default")
      (node (ref "F1") (pin "2") (pinfunction "2_2") (pintype "bidirectional"))
      (node (ref "L2") (pin "1") (pinfunction "1_1") (pintype "passive"))
    )
    (net (code "35") (name "Net-(F2-Pad1)") (class "Default")
      (node (ref "F2") (pin "1") (pinfunction "1_1") (pintype "bidirectional"))
      (node (ref "JP2") (pin "2") (pinfunction "2_2") (pintype "passive"))
    )
    (net (code "36") (name "Net-(F2-Pad2)") (class "Default")
      (node (ref "F2") (pin "2") (pinfunction "2_2") (pintype "bidirectional"))
      (node (ref "L3") (pin "1") (pinfunction "1_1") (pintype "passive"))
    )
    (net (code "37") (name "Net-(J1A-S)") (class "Default")
      (node (ref "J1") (pin "1") (pinfunction "S_1") (pintype "passive"))
      (node (ref "Q2") (pin "1") (pinfunction "D_1") (pintype "passive"))
      (node (ref "Q2") (pin "2") (pinfunction "D1_2") (pintype "passive"))
      (node (ref "Q2") (pin "5") (pinfunction "D2_5") (pintype "passive"))
      (node (ref "Q2") (pin "6") (pinfunction "D3_6") (pintype "passive"))
    )
    (net (code "38") (name "Net-(J1B-S)") (class "Default")
      (node (ref "J1") (pin "10") (pinfunction "S_10") (pintype "passive"))
      (node (ref "U2") (pin "1") (pinfunction "B2_1") (pintype "bidirectional"))
    )
    (net (code "39") (name "Net-(J1C-S)") (class "Default")
      (node (ref "J1") (pin "11") (pinfunction "S_11") (pintype "passive"))
      (node (ref "U2") (pin "8") (pinfunction "B1_8") (pintype "bidirectional"))
    )
    (net (code "40") (name "Net-(J1D-S)") (class "Default")
      (node (ref "J1") (pin "12") (pinfunction "S_12") (pintype "passive"))
      (node (ref "U3") (pin "8") (pinfunction "B1_8") (pintype "bidirectional"))
    )
    (net (code "41") (name "Net-(J1H-S)") (class "Default")
      (node (ref "J1") (pin "2") (pinfunction "S_2") (pintype "passive"))
      (node (ref "L2") (pin "2") (pinfunction "2_2") (pintype "passive"))
    )
    (net (code "42") (name "Net-(J1L-S)") (class "Default")
      (node (ref "J1") (pin "6") (pinfunction "S_6") (pintype "passive"))
      (node (ref "R10") (pin "2") (pinfunction "2_2") (pintype "passive"))
    )
    (net (code "43") (name "Net-(J1O-S)") (class "Default")
      (node (ref "J1") (pin "9") (pinfunction "S_9") (pintype "passive"))
      (node (ref "U3") (pin "1") (pinfunction "B2_1") (pintype "bidirectional"))
    )
    (net (code "44") (name "Net-(J2D-S)") (class "Default")
      (node (ref "J2") (pin "12") (pinfunction "S_12") (pintype "passive"))
      (node (ref "J3") (pin "12") (pinfunction "S_12") (pintype "passive"))
    )
    (net (code "45") (name "Net-(J4A-S)") (class "Default")
      (node (ref "J4") (pin "1") (pinfunction "S_1") (pintype "passive"))
      (node (ref "L3") (pin "2") (pinfunction "2_2") (pintype "passive"))
    )
    (net (code "46") (name "Net-(J4B-S)") (class "Default")
      (node (ref "J4") (pin "2") (pinfunction "S_2") (pintype "passive"))
      (node (ref "L5") (pin "2") (pinfunction "2_2") (pintype "passive"))
    )
    (net (code "47") (name "Net-(J4C-S)") (class "Default")
      (node (ref "J4") (pin "3") (pinfunction "S_3") (pintype "passive"))
      (node (ref "L4") (pin "2") (pinfunction "2_2") (pintype "passive"))
    )
    (net (code "48") (name "Net-(J5-2)") (class "Default")
      (node (ref "J5") (pin "D-") (pinfunction "2_D-") (pintype "bidirectional"))
      (node (ref "R6") (pin "1") (pinfunction "1_1") (pintype "passive"))
    )
    (net (code "49") (name "Net-(J5-3)") (class "Default")
      (node (ref "J5") (pin "D+") (pinfunction "3_D+") (pintype "bidirectional"))
      (node (ref "R8") (pin "1") (pinfunction "1_1") (pintype "passive"))
    )
    (net (code "50") (name "Net-(J7B-S)") (class "Default")
      (node (ref "J7") (pin "2") (pinfunction "S_2") (pintype "passive"))
      (node (ref "Q3") (pin "3") (pinfunction "D_3") (pintype "passive"))
      (node (ref "R22") (pin "1") (pinfunction "1_1") (pintype "passive"))
    )
    (net (code "51") (name "Net-(L10-Pad1)") (class "Default")
      (node (ref "L10") (pin "1") (pinfunction "1_1") (pintype "passive"))
      (node (ref "R11") (pin "2") (pinfunction "2_2") (pintype "passive"))
    )
    (net (code "52") (name "Net-(LED1-PadC)") (class "Default")
      (node (ref "LED1") (pin "C") (pinfunction "C_C") (pintype "passive"))
      (node (ref "R13") (pin "2") (pinfunction "2_2") (pintype "passive"))
    )
    (net (code "53") (name "Net-(LED2-PadC)") (class "Default")
      (node (ref "LED2") (pin "C") (pinfunction "C_C") (pintype "passive"))
      (node (ref "R14") (pin "2") (pinfunction "2_2") (pintype "passive"))
    )
    (net (code "54") (name "Net-(LED3-PadC)") (class "Default")
      (node (ref "LED3") (pin "C") (pinfunction "C_C") (pintype "passive"))
      (node (ref "R15") (pin "2") (pinfunction "2_2") (pintype "passive"))
    )
    (net (code "55") (name "Net-(Q2-S)") (class "Default")
      (node (ref "L1") (pin "2") (pinfunction "2_2") (pintype "passive"))
      (node (ref "Q2") (pin "4") (pinfunction "S_4") (pintype "passive"))
    )
    (net (code "56") (name "Net-(U$5-CLK)") (class "Default")
      (node (ref "RN1") (pin "8") (pinfunction "8_8") (pintype "passive"))
      (node (ref "U$5") (pin "5") (pinfunction "CLK_5") (pintype "bidirectional"))
    )
    (net (code "57") (name "Net-(U$5-CS)") (class "Default")
      (node (ref "RN1") (pin "5") (pinfunction "5_5") (pintype "passive"))
      (node (ref "U$5") (pin "2") (pinfunction "CS_2") (pintype "bidirectional"))
    )
    (net (code "58") (name "Net-(U$5-DI)") (class "Default")
      (node (ref "RN1") (pin "6") (pinfunction "6_6") (pintype "passive"))
      (node (ref "U$5") (pin "3") (pinfunction "DI_3") (pintype "bidirectional"))
    )
    (net (code "59") (name "Net-(U$5-DO)") (class "Default")
      (node (ref "RN1") (pin "7") (pinfunction "7_7") (pintype "passive"))
      (node (ref "U$5") (pin "7") (pinfunction "DO_7") (pintype "bidirectional"))
    )
    (net (code "60") (name "Net-(U1H-PH0{slash}OSC<=)") (class "Default")
      (node (ref "C3") (pin "1") (pinfunction "1_1") (pintype "passive"))
      (node (ref "U1") (pin "5") (pinfunction "PH0/OSC<=_5") (pintype "bidirectional"))
      (node (ref "X1") (pin "3") (pinfunction "3_3") (pintype "bidirectional"))
    )
    (net (code "61") (name "Net-(U1H-PH1{slash}OSC=>)") (class "Default")
      (node (ref "C4") (pin "2") (pinfunction "2_2") (pintype "passive"))
      (node (ref "U1") (pin "6") (pinfunction "PH1/OSC=>_6") (pintype "bidirectional"))
      (node (ref "X1") (pin "1") (pinfunction "1_1") (pintype "bidirectional"))
    )
    (net (code "62") (name "Net-(U1I-VCAP_1)") (class "Default")
      (node (ref "C11") (pin "1") (pinfunction "1_1") (pintype "passive"))
      (node (ref "U1") (pin "31") (pinfunction "VCAP_1_31") (pintype "power_in"))
    )
    (net (code "63") (name "Net-(U1I-VCAP_2)") (class "Default")
      (node (ref "C12") (pin "1") (pinfunction "1_1") (pintype "passive"))
      (node (ref "U1") (pin "47") (pinfunction "VCAP_2_47") (pintype "power_in"))
    )
    (net (code "64") (name "Net-(U1J-BOOT0)") (class "Default")
      (node (ref "BOOT0") (pin "P$1") (pinfunction "P$1_P$1") (pintype "passive"))
      (node (ref "R18") (pin "2") (pinfunction "2_2") (pintype "passive"))
      (node (ref "U1") (pin "60") (pinfunction "BOOT0_60") (pintype "input"))
    )
    (net (code "65") (name "Net-(U7-BP)") (class "Default")
      (node (ref "C16") (pin "1") (pinfunction "1_1") (pintype "passive"))
      (node (ref "U7") (pin "4") (pinfunction "BP_4") (pintype "input"))
    )
    (net (code "66") (name "Net-(U7-EN)") (class "Default")
      (node (ref "C14") (pin "1") (pinfunction "1_1") (pintype "passive"))
      (node (ref "L11") (pin "2") (pinfunction "2_2") (pintype "passive"))
      (node (ref "U7") (pin "1") (pinfunction "IN_1") (pintype "input"))
      (node (ref "U7") (pin "3") (pinfunction "EN_3") (pintype "input"))
    )
    (net (code "67") (name "Net-(U11-C1)") (class "Default")
      (node (ref "C23") (pin "1") (pinfunction "1_1") (pintype "passive"))
      (node (ref "U11") (pin "10") (pinfunction "C1_10") (pintype "bidirectional"))
    )
    (net (code "68") (name "Net-(U11-SETC)") (class "Default")
      (node (ref "C24") (pin "2") (pinfunction "2_2") (pintype "passive"))
      (node (ref "U11") (pin "12") (pinfunction "SETC_12") (pintype "bidirectional"))
    )
    (net (code "69") (name "Net-(U11-SETP)") (class "Default")
      (node (ref "C24") (pin "1") (pinfunction "1_1") (pintype "passive"))
      (node (ref "U11") (pin "8") (pinfunction "SETP_8") (pintype "bidirectional"))
    )
    (net (code "70") (name "Net-(U12-PLLFILT)") (class "Default")
      (node (ref "C25") (pin "1") (pinfunction "1_1") (pintype "passive"))
      (node (ref "U12") (pin "14") (pinfunction "PLLFILT_14") (pintype "bidirectional"))
    )
    (net (code "71") (name "Net-(U14-CPOUT)") (class "Default")
      (node (ref "C20") (pin "1") (pinfunction "1_1") (pintype "passive"))
      (node (ref "U14") (pin "20") (pinfunction "CPOUT_20") (pintype "bidirectional"))
    )
    (net (code "72") (name "Net-(U14-INT)") (class "Default")
      (node (ref "JP6") (pin "2") (pinfunction "2_2") (pintype "passive"))
      (node (ref "U14") (pin "12") (pinfunction "INT_12") (pintype "bidirectional"))
    )
    (net (code "73") (name "Net-(U14-REGOUT)") (class "Default")
      (node (ref "C26") (pin "1") (pinfunction "1_1") (pintype "passive"))
      (node (ref "U14") (pin "10") (pinfunction "REGOUT_10") (pintype "bidirectional"))
    )
    (net (code "74") (name "OTG_FS_DM") (class "Default")
      (node (ref "R6") (pin "2") (pinfunction "2_2") (pintype "passive"))
      (node (ref "U1") (pin "44") (pinfunction "PA11_44") (pintype "bidirectional"))
    )
    (net (code "75") (name "OTG_FS_DP") (class "Default")
      (node (ref "R8") (pin "2") (pinfunction "2_2") (pintype "passive"))
      (node (ref "U1") (pin "45") (pinfunction "PA12_45") (pintype "bidirectional"))
    )
    (net (code "76") (name "PB2-BOOT1") (class "Default")
      (node (ref "R5") (pin "1") (pinfunction "1_1") (pintype "passive"))
      (node (ref "U1") (pin "28") (pinfunction "PB2_28") (pintype "bidirectional"))
    )
    (net (code "77") (name "PPM_INPUT") (class "Default")
      (node (ref "J2") (pin "23") (pinfunction "S_23") (pintype "passive"))
      (node (ref "J3") (pin "23") (pinfunction "S_23") (pintype "passive"))
      (node (ref "R10") (pin "1") (pinfunction "1_1") (pintype "passive"))
      (node (ref "U1") (pin "43") (pinfunction "PA10_43") (pintype "bidirectional"))
    )
    (net (code "78") (name "RESET") (class "Default")
      (node (ref "!RESET") (pin "P$1") (pinfunction "P$1_P$1") (pintype "passive"))
      (node (ref "C17") (pin "2") (pinfunction "2_2") (pintype "passive"))
      (node (ref "R16") (pin "1") (pinfunction "1_1") (pintype "passive"))
      (node (ref "S1") (pin "A1") (pinfunction "1_A1") (pintype "passive"))
      (node (ref "U1") (pin "7") (pinfunction "NRST_7") (pintype "input"))
    )
    (net (code "79") (name "SPI1_MISO") (class "Default")
      (node (ref "SPI1_MISO") (pin "P$1") (pinfunction "P$1_P$1") (pintype "passive"))
      (node (ref "U1") (pin "22") (pinfunction "PA6_22") (pintype "bidirectional"))
      (node (ref "U12") (pin "4") (pinfunction "SDO/SA0_4") (pintype "bidirectional"))
      (node (ref "U14") (pin "9") (pinfunction "AD0/SDO_9") (pintype "bidirectional"))
    )
    (net (code "80") (name "SPI1_MOSI") (class "Default")
      (node (ref "SPI1_MOSI") (pin "P$1") (pinfunction "P$1_P$1") (pintype "passive"))
      (node (ref "U1") (pin "23") (pinfunction "PA7_23") (pintype "bidirectional"))
      (node (ref "U12") (pin "3") (pinfunction "SDA/SDI/SDO_3") (pintype "bidirectional"))
      (node (ref "U14") (pin "24") (pinfunction "SDA/SDI_24") (pintype "bidirectional"))
    )
    (net (code "81") (name "SPI1_SCK") (class "Default")
      (node (ref "SPI1_SCK") (pin "P$1") (pinfunction "P$1_P$1") (pintype "passive"))
      (node (ref "U1") (pin "21") (pinfunction "PA5_21") (pintype "bidirectional"))
      (node (ref "U12") (pin "2") (pinfunction "SCL/SPC_2") (pintype "input"))
      (node (ref "U14") (pin "23") (pinfunction "SCL/SCLK_23") (pintype "bidirectional"))
    )
    (net (code "82") (name "SPI3_MISO") (class "Default")
      (node (ref "R23") (pin "1") (pinfunction "1_1") (pintype "passive"))
      (node (ref "RN1") (pin "2") (pinfunction "2_2") (pintype "passive"))
      (node (ref "U1") (pin "52") (pinfunction "PC11_52") (pintype "bidirectional"))
    )
    (net (code "83") (name "SPI3_MOSI") (class "Default")
      (node (ref "RN1") (pin "3") (pinfunction "3_3") (pintype "passive"))
      (node (ref "U1") (pin "57") (pinfunction "PB5_57") (pintype "bidirectional"))
    )
    (net (code "84") (name "SPI3_NSS") (class "Default")
      (node (ref "RN1") (pin "4") (pinfunction "4_4") (pintype "passive"))
      (node (ref "U1") (pin "20") (pinfunction "PA4_20") (pintype "bidirectional"))
    )
    (net (code "85") (name "SPI3_SCK") (class "Default")
      (node (ref "RN1") (pin "1") (pinfunction "1_1") (pintype "passive"))
      (node (ref "U1") (pin "51") (pinfunction "PC10_51") (pintype "bidirectional"))
    )
    (net (code "86") (name "UART5_RX") (class "Default")
      (node (ref "J2") (pin "16") (pinfunction "S_16") (pintype "passive"))
      (node (ref "J3") (pin "16") (pinfunction "S_16") (pintype "passive"))
      (node (ref "U1") (pin "54") (pinfunction "PD2_54") (pintype "bidirectional"))
    )
    (net (code "87") (name "UART5_TX") (class "Default")
      (node (ref "J2") (pin "15") (pinfunction "S_15") (pintype "passive"))
      (node (ref "J3") (pin "15") (pinfunction "S_15") (pintype "passive"))
      (node (ref "U1") (pin "53") (pinfunction "PC12_53") (pintype "bidirectional"))
    )
    (net (code "88") (name "USART1_RX") (class "Default")
      (node (ref "U1") (pin "59") (pinfunction "PB7_59") (pintype "bidirectional"))
      (node (ref "U4") (pin "4") (pinfunction "A2_4") (pintype "bidirectional"))
    )
    (net (code "89") (name "USART1_RX_EXT") (class "Default")
      (node (ref "J1") (pin "7") (pinfunction "S_7") (pintype "passive"))
      (node (ref "J2") (pin "8") (pinfunction "S_8") (pintype "passive"))
      (node (ref "J3") (pin "8") (pinfunction "S_8") (pintype "passive"))
      (node (ref "U4") (pin "1") (pinfunction "B2_1") (pintype "bidirectional"))
    )
    (net (code "90") (name "USART1_TX") (class "Default")
      (node (ref "U1") (pin "58") (pinfunction "PB6_58") (pintype "bidirectional"))
      (node (ref "U4") (pin "5") (pinfunction "A1_5") (pintype "bidirectional"))
    )
    (net (code "91") (name "USART1_TX_EXT") (class "Default")
      (node (ref "J1") (pin "8") (pinfunction "S_8") (pintype "passive"))
      (node (ref "J2") (pin "7") (pinfunction "S_7") (pintype "passive"))
      (node (ref "J3") (pin "7") (pinfunction "S_7") (pintype "passive"))
      (node (ref "U4") (pin "8") (pinfunction "B1_8") (pintype "bidirectional"))
    )
    (net (code "92") (name "USART2_CTS") (class "Default")
      (node (ref "J2") (pin "19") (pinfunction "S_19") (pintype "passive"))
      (node (ref "J3") (pin "19") (pinfunction "S_19") (pintype "passive"))
      (node (ref "U1") (pin "14") (pinfunction "PA0_14") (pintype "bidirectional"))
      (node (ref "U2") (pin "5") (pinfunction "A1_5") (pintype "bidirectional"))
    )
    (net (code "93") (name "USART2_RTS") (class "Default")
      (node (ref "J2") (pin "20") (pinfunction "S_20") (pintype "passive"))
      (node (ref "J3") (pin "20") (pinfunction "S_20") (pintype "passive"))
      (node (ref "U1") (pin "15") (pinfunction "PA1_15") (pintype "bidirectional"))
      (node (ref "U2") (pin "4") (pinfunction "A2_4") (pintype "bidirectional"))
    )
    (net (code "94") (name "USART2_RX") (class "Default")
      (node (ref "J2") (pin "22") (pinfunction "S_22") (pintype "passive"))
      (node (ref "J3") (pin "22") (pinfunction "S_22") (pintype "passive"))
      (node (ref "U1") (pin "17") (pinfunction "PA3_17") (pintype "bidirectional"))
      (node (ref "U3") (pin "4") (pinfunction "A2_4") (pintype "bidirectional"))
    )
    (net (code "95") (name "USART2_TX") (class "Default")
      (node (ref "J2") (pin "21") (pinfunction "S_21") (pintype "passive"))
      (node (ref "J3") (pin "21") (pinfunction "S_21") (pintype "passive"))
      (node (ref "U1") (pin "16") (pinfunction "PA2_16") (pintype "bidirectional"))
      (node (ref "U3") (pin "5") (pinfunction "A1_5") (pintype "bidirectional"))
    )
    (net (code "96") (name "USART6_RX") (class "Default")
      (node (ref "J2") (pin "14") (pinfunction "S_14") (pintype "passive"))
      (node (ref "J3") (pin "14") (pinfunction "S_14") (pintype "passive"))
      (node (ref "L4") (pin "1") (pinfunction "1_1") (pintype "passive"))
      (node (ref "U1") (pin "38") (pinfunction "PC7_38") (pintype "bidirectional"))
      (node (ref "USART6_RX") (pin "P$1") (pinfunction "P$1_P$1") (pintype "passive"))
    )
    (net (code "97") (name "USART6_TX") (class "Default")
      (node (ref "J2") (pin "13") (pinfunction "S_13") (pintype "passive"))
      (node (ref "J3") (pin "13") (pinfunction "S_13") (pintype "passive"))
      (node (ref "L5") (pin "1") (pinfunction "1_1") (pintype "passive"))
      (node (ref "U1") (pin "37") (pinfunction "PC6_37") (pintype "bidirectional"))
      (node (ref "USART6_TX") (pin "P$1") (pinfunction "P$1_P$1") (pintype "passive"))
    )
    (net (code "98") (name "VBAT_IN") (class "Default")
      (node (ref "D2") (pin "1") (pinfunction "A1_1") (pintype "passive"))
      (node (ref "J1") (pin "5") (pinfunction "S_5") (pintype "passive"))
      (node (ref "L10") (pin "2") (pinfunction "2_2") (pintype "passive"))
    )
    (net (code "99") (name "VBUS") (class "Default")
      (node (ref "J5") (pin "VBUS") (pinfunction "1_VBUS") (pintype "power_in"))
      (node (ref "L8") (pin "2") (pinfunction "2_2") (pintype "passive"))
      (node (ref "U1") (pin "42") (pinfunction "PA9_42") (pintype "bidirectional"))
    )
    (net (code "100") (name "VDD_3V3") (class "Default")
      (node (ref "C10") (pin "1") (pinfunction "1_1") (pintype "passive"))
      (node (ref "C2") (pin "1") (pinfunction "1_1") (pintype "passive"))
      (node (ref "C6") (pin "A") (pinfunction "+_A") (pintype "passive"))
      (node (ref "C8") (pin "1") (pinfunction "1_1") (pintype "passive"))
      (node (ref "C9") (pin "1") (pinfunction "1_1") (pintype "passive"))
      (node (ref "F1") (pin "1") (pinfunction "1_1") (pintype "bidirectional"))
      (node (ref "J6") (pin "1") (pinfunction "S_1") (pintype "passive"))
      (node (ref "JP1") (pin "1") (pinfunction "1_1") (pintype "passive"))
      (node (ref "JP2") (pin "3") (pinfunction "3_3") (pintype "passive"))
      (node (ref "LED1") (pin "A") (pinfunction "A_A") (pintype "passive"))
      (node (ref "LED2") (pin "A") (pinfunction "A_A") (pintype "passive"))
      (node (ref "LED3") (pin "A") (pinfunction "A_A") (pintype "passive"))
      (node (ref "R16") (pin "2") (pinfunction "2_2") (pintype "passive"))
      (node (ref "R19") (pin "2") (pinfunction "2_2") (pintype "passive"))
      (node (ref "R20") (pin "2") (pinfunction "2_2") (pintype "passive"))
      (node (ref "R23") (pin "2") (pinfunction "2_2") (pintype "passive"))
      (node (ref "R7") (pin "2") (pinfunction "2_2") (pintype "passive"))
      (node (ref "R9") (pin "2") (pinfunction "2_2") (pintype "passive"))
      (node (ref "U$5") (pin "4") (pinfunction "VCC_4") (pintype "passive"))
      (node (ref "U1") (pin "1") (pinfunction "VBAT_1") (pintype "power_in"))
      (node (ref "U1") (pin "19") (pinfunction "VDD_4_19") (pintype "power_in"))
      (node (ref "U1") (pin "32") (pinfunction "VDD_1_32") (pintype "power_in"))
      (node (ref "U1") (pin "48") (pinfunction "VDD_2_48") (pintype "power_in"))
      (node (ref "U1") (pin "64") (pinfunction "VDD_3_64") (pintype "power_in"))
      (node (ref "U12") (pin "1") (pinfunction "VDD_IO_1") (pintype "bidirectional"))
      (node (ref "U2") (pin "3") (pinfunction "VCCA_3") (pintype "input"))
      (node (ref "U2") (pin "6") (pinfunction "OE_6") (pintype "input"))
      (node (ref "U3") (pin "3") (pinfunction "VCCA_3") (pintype "input"))
      (node (ref "U3") (pin "6") (pinfunction "OE_6") (pintype "input"))
      (node (ref "U4") (pin "3") (pinfunction "VCCA_3") (pintype "input"))
      (node (ref "U4") (pin "6") (pinfunction "OE_6") (pintype "input"))
      (node (ref "U4") (pin "7") (pinfunction "VCCB_7") (pintype "input"))
      (node (ref "U5") (pin "1") (pinfunction "VCCA_1") (pintype "passive"))
      (node (ref "U6") (pin "2") (pinfunction "VOUT_2") (pintype "bidirectional"))
      (node (ref "U6") (pin "4") (pinfunction "VOUT-TAB_4") (pintype "bidirectional"))
      (node (ref "U8") (pin "8") (pinfunction "VCC_8") (pintype "power_in"))
      (node (ref "VDD_3V3") (pin "P$1") (pinfunction "P$1_P$1") (pintype "passive"))
    )
    (net (code "101") (name "VDD_3V3_ANALOG") (class "Default")
      (node (ref "C13") (pin "A") (pinfunction "+_A") (pintype "passive"))
      (node (ref "C15") (pin "1") (pinfunction "1_1") (pintype "passive"))
      (node (ref "C18") (pin "1") (pinfunction "1_1") (pintype "passive"))
      (node (ref "C19") (pin "1") (pinfunction "1_1") (pintype "passive"))
      (node (ref "C21") (pin "1") (pinfunction "1_1") (pintype "passive"))
      (node (ref "C22") (pin "1") (pinfunction "1_1") (pintype "passive"))
      (node (ref "C28") (pin "1") (pinfunction "1_1") (pintype "passive"))
      (node (ref "U1") (pin "13") (pinfunction "VDDA_13") (pintype "power_in"))
      (node (ref "U10") (pin "1") (pinfunction "VDD_1") (pintype "bidirectional"))
      (node (ref "U10") (pin "2") (pinfunction "PS_2") (pintype "bidirectional"))
      (node (ref "U10") (pin "4") (pinfunction "CSB1_4") (pintype "bidirectional"))
      (node (ref "U10") (pin "5") (pinfunction "CSB2_5") (pintype "bidirectional"))
      (node (ref "U11") (pin "13") (pinfunction "VDDIO_13") (pintype "bidirectional"))
      (node (ref "U11") (pin "2") (pinfunction "VDD_2") (pintype "bidirectional"))
      (node (ref "U11") (pin "4") (pinfunction "S1_VDDIO_4") (pintype "bidirectional"))
      (node (ref "U12") (pin "15") (pinfunction "RES_P15_VDD_15") (pintype "bidirectional"))
      (node (ref "U12") (pin "16") (pinfunction "VDD_16") (pintype "bidirectional"))
      (node (ref "U14") (pin "13") (pinfunction "VDD_13") (pintype "bidirectional"))
      (node (ref "U7") (pin "5") (pinfunction "OUT_5") (pintype "passive"))
      (node (ref "VDDA_3V3") (pin "P$1") (pinfunction "P$1_P$1") (pintype "passive"))
    )
    (net (code "102") (name "VDD_5V") (class "Default")
      (node (ref "C27") (pin "A") (pinfunction "+_A") (pintype "passive"))
      (node (ref "C7") (pin "1") (pinfunction "1_1") (pintype "passive"))
      (node (ref "D2") (pin "2") (pinfunction "A2_2") (pintype "passive"))
      (node (ref "JP1") (pin "3") (pinfunction "3_3") (pintype "passive"))
      (node (ref "JP2") (pin "1") (pinfunction "1_1") (pintype "passive"))
      (node (ref "L1") (pin "1") (pinfunction "1_1") (pintype "passive"))
      (node (ref "L11") (pin "1") (pinfunction "1_1") (pintype "passive"))
      (node (ref "Q1") (pin "4") (pinfunction "S_4") (pintype "passive"))
      (node (ref "R1") (pin "2") (pinfunction "2_2") (pintype "passive"))
      (node (ref "R2") (pin "2") (pinfunction "2_2") (pintype "passive"))
      (node (ref "U6") (pin "3") (pinfunction "VIN_3") (pintype "bidirectional"))
    )
    (net (code "103") (name "VDD_5V_IN") (class "Default")
      (node (ref "D1") (pin "CATHODE") (pinfunction "C_CATHODE") (pintype "passive"))
      (node (ref "J2") (pin "1") (pinfunction "S_1") (pintype "passive"))
      (node (ref "J2") (pin "2") (pinfunction "S_2") (pintype "passive"))
      (node (ref "J3") (pin "1") (pinfunction "S_1") (pintype "passive"))
      (node (ref "J3") (pin "2") (pinfunction "S_2") (pintype "passive"))
      (node (ref "Q1") (pin "1") (pinfunction "D_1") (pintype "passive"))
      (node (ref "Q1") (pin "2") (pinfunction "D1_2") (pintype "passive"))
      (node (ref "Q1") (pin "5") (pinfunction "D2_5") (pintype "passive"))
      (node (ref "Q1") (pin "6") (pinfunction "D3_6") (pintype "passive"))
    )
    (net (code "104") (name "VDD_IO") (class "Default")
      (node (ref "C1") (pin "1") (pinfunction "1_1") (pintype "passive"))
      (node (ref "JP1") (pin "2") (pinfunction "2_2") (pintype "passive"))
      (node (ref "U2") (pin "7") (pinfunction "VCCB_7") (pintype "input"))
      (node (ref "U3") (pin "7") (pinfunction "VCCB_7") (pintype "input"))
      (node (ref "U5") (pin "8") (pinfunction "VCCB_8") (pintype "passive"))
    )
    (net (code "105") (name "unconnected-(J4D-S-Pad4)") (class "Default")
      (node (ref "J4") (pin "4") (pinfunction "S_4") (pintype "passive"))
    )
    (net (code "106") (name "unconnected-(J5-4-PadID)") (class "Default")
      (node (ref "J5") (pin "ID") (pinfunction "4_ID") (pintype "passive"))
    )
    (net (code "107") (name "unconnected-(U8-WP-Pad7)") (class "Default")
      (node (ref "U8") (pin "7") (pinfunction "WP_7") (pintype "bidirectional"))
    )
    (net (code "108") (name "unconnected-(U10-SDO-Pad6)") (class "Default")
      (node (ref "U10") (pin "6") (pinfunction "SDO_6") (pintype "bidirectional"))
    )
    (net (code "109") (name "unconnected-(U11-NC_P3-Pad3)") (class "Default")
      (node (ref "U11") (pin "3") (pinfunction "NC_P3_3") (pintype "no_connect"))
    )
    (net (code "110") (name "unconnected-(U11-NC_P5-Pad5)") (class "Default")
      (node (ref "U11") (pin "5") (pinfunction "NC_P5_5") (pintype "no_connect"))
    )
    (net (code "111") (name "unconnected-(U11-NC_P6-Pad6)") (class "Default")
      (node (ref "U11") (pin "6") (pinfunction "NC_P6_6") (pintype "no_connect"))
    )
    (net (code "112") (name "unconnected-(U11-NC_P7-Pad7)") (class "Default")
      (node (ref "U11") (pin "7") (pinfunction "NC_P7_7") (pintype "no_connect"))
    )
    (net (code "113") (name "unconnected-(U11-NC_P14-Pad14)") (class "Default")
      (node (ref "U11") (pin "14") (pinfunction "NC_P14_14") (pintype "no_connect"))
    )
    (net (code "114") (name "unconnected-(U12-DRDY{slash}INT2-Pad6)") (class "Default")
      (node (ref "U12") (pin "6") (pinfunction "DRDY/INT2_6") (pintype "output"))
    )
    (net (code "115") (name "unconnected-(U12-INT1-Pad7)") (class "Default")
      (node (ref "U12") (pin "7") (pinfunction "INT1_7") (pintype "output"))
    )
    (net (code "116") (name "unconnected-(U14-AUX_CL-Pad7)") (class "Default")
      (node (ref "U14") (pin "7") (pinfunction "AUX_CL_7") (pintype "bidirectional"))
    )
    (net (code "117") (name "unconnected-(U14-AUX_DA-Pad6)") (class "Default")
      (node (ref "U14") (pin "6") (pinfunction "AUX_DA_6") (pintype "bidirectional"))
    )
    (net (code "118") (name "unconnected-(U14-CLKOUT-Pad22)") (class "Default")
      (node (ref "U14") (pin "22") (pinfunction "CLKOUT_22") (pintype "bidirectional"))
    )
    (net (code "119") (name "unconnected-(U14-NC1-Pad2)") (class "Default")
      (node (ref "U14") (pin "2") (pinfunction "NC1_2") (pintype "bidirectional"))
    )
    (net (code "120") (name "unconnected-(U14-NC2-Pad3)") (class "Default")
      (node (ref "U14") (pin "3") (pinfunction "NC2_3") (pintype "bidirectional"))
    )
    (net (code "121") (name "unconnected-(U14-NC3-Pad4)") (class "Default")
      (node (ref "U14") (pin "4") (pinfunction "NC3_4") (pintype "bidirectional"))
    )
    (net (code "122") (name "unconnected-(U14-NC4-Pad5)") (class "Default")
      (node (ref "U14") (pin "5") (pinfunction "NC4_5") (pintype "bidirectional"))
    )
    (net (code "123") (name "unconnected-(U14-NC5-Pad14)") (class "Default")
      (node (ref "U14") (pin "14") (pinfunction "NC5_14") (pintype "bidirectional"))
    )
    (net (code "124") (name "unconnected-(U14-NC6-Pad15)") (class "Default")
      (node (ref "U14") (pin "15") (pinfunction "NC6_15") (pintype "bidirectional"))
    )
    (net (code "125") (name "unconnected-(U14-NC7-Pad16)") (class "Default")
      (node (ref "U14") (pin "16") (pinfunction "NC7_16") (pintype "bidirectional"))
    )
    (net (code "126") (name "unconnected-(U14-NC8-Pad17)") (class "Default")
      (node (ref "U14") (pin "17") (pinfunction "NC8_17") (pintype "bidirectional"))
    )
    (net (code "127") (name "unconnected-(U14-RESV1-Pad19)") (class "Default")
      (node (ref "U14") (pin "19") (pinfunction "RESV1_19") (pintype "bidirectional"))
    )
    (net (code "128") (name "unconnected-(U14-RESV2-Pad21)") (class "Default")
      (node (ref "U14") (pin "21") (pinfunction "RESV2_21") (pintype "bidirectional"))
    )
    (net (code "129") (name "~{JTRST}") (class "Default")
      (node (ref "!JTRST") (pin "P$1") (pinfunction "P$1_P$1") (pintype "passive"))
      (node (ref "J6") (pin "10") (pinfunction "S_10") (pintype "passive"))
      (node (ref "U1") (pin "56") (pinfunction "PB4_56") (pintype "bidirectional"))
    )
  )
)
